# CM5_Adapter.net
KiCad netlist of a schematic drawn in Altium Designer
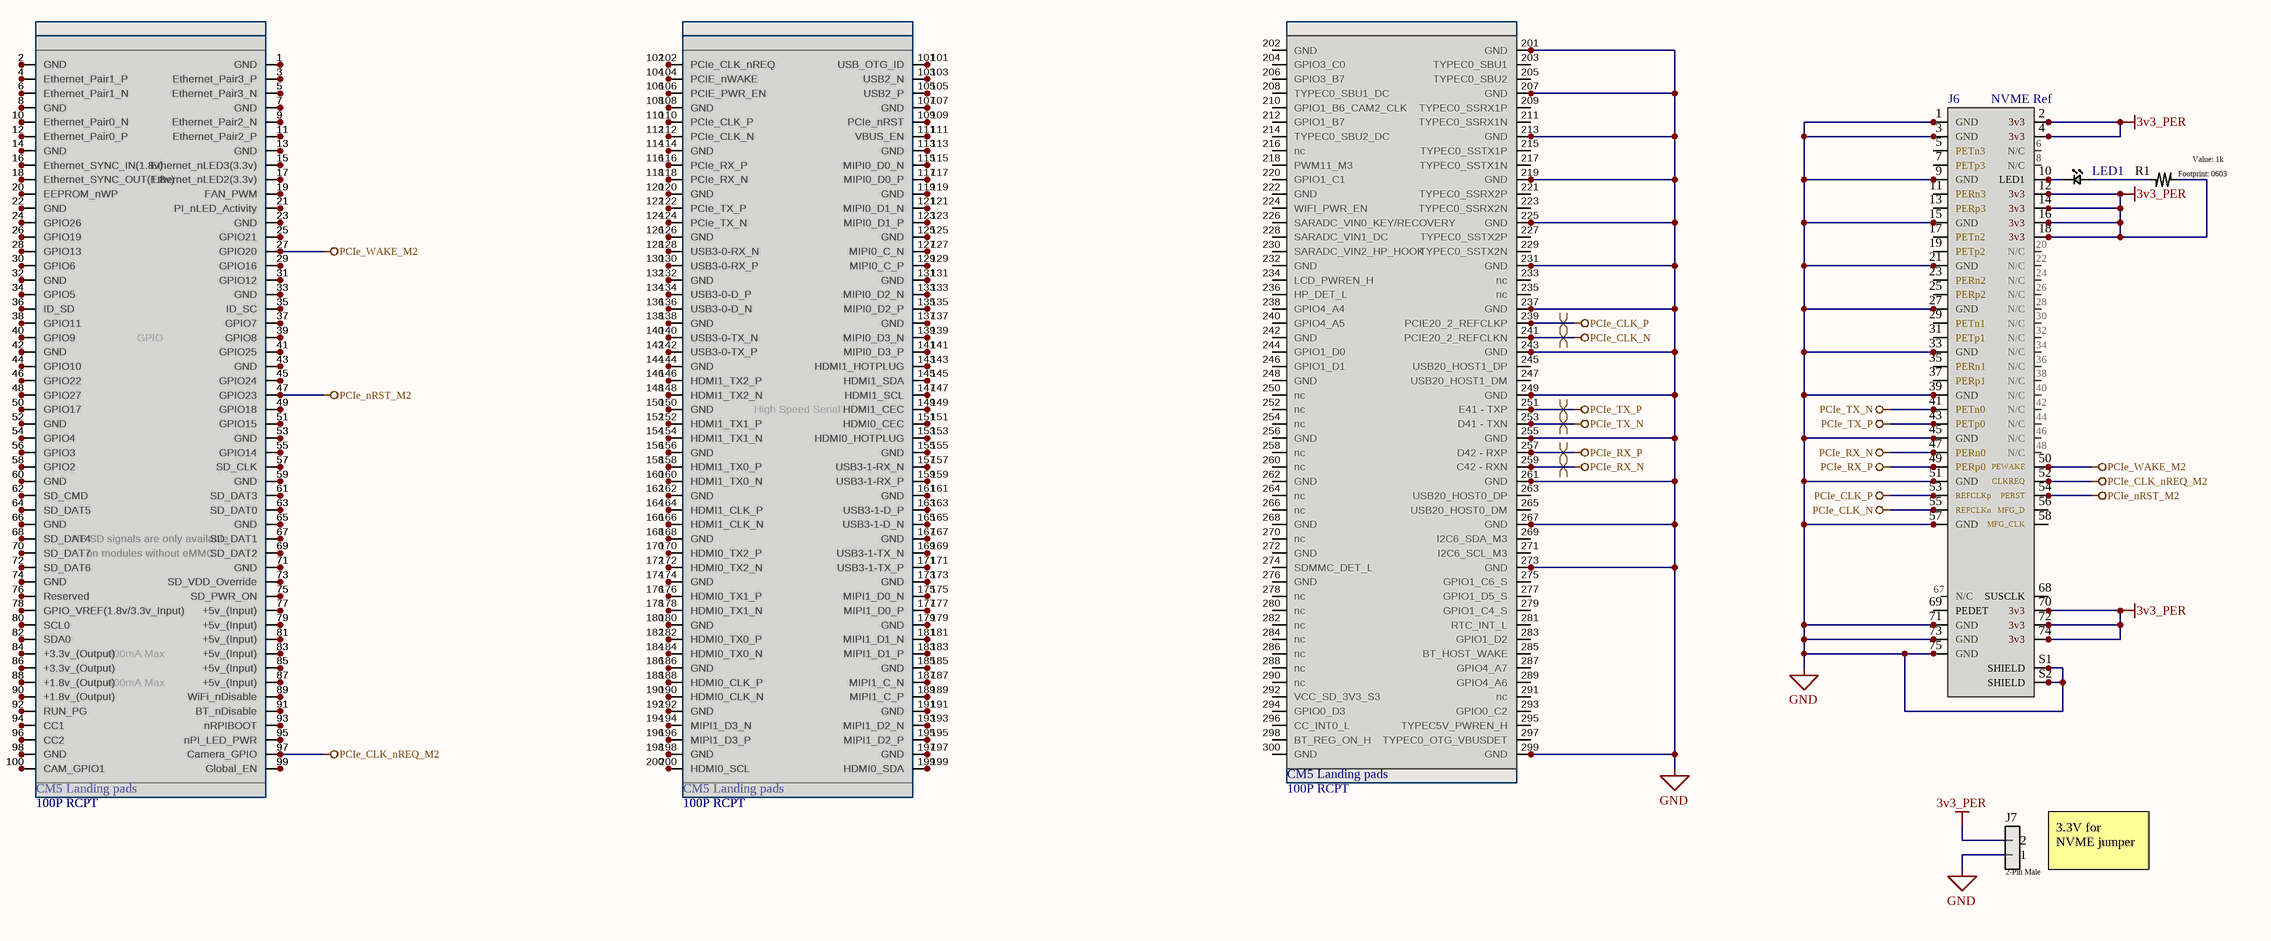
[diagram p0: CM5 Adapter.SchDoc]

(export (version "E")
  (design (tool "Eeschema 10.0.6"))
  (components
    (comp (ref "J1")
      (value "100P RCPT")
      (footprint "DF40C-100DP-0.4V(51)")
      (description "100 Position Connector Receptacle, Center Strip Contacts Surface Mount Gold")
      (fields (field (name "MF") "Hirose") (field (name "MP") "DF40C-100DS-0.4V(51)"))
      (libsource (lib "SOC_Carrier") (part "DF40-XX-100DS RCPT"))
    )
    (comp (ref "J2")
      (value "100P RCPT")
      (footprint "DF40C-100DP-0.4V(51)")
      (description "100 Position Connector Receptacle, Center Strip Contacts Surface Mount Gold")
      (fields (field (name "MF") "Hirose") (field (name "MP") "DF40C-100DS-0.4V(51)"))
      (libsource (lib "SOC_Carrier") (part "DF40-XX-100DS RCPT"))
    )
    (comp (ref "J3")
      (value "100P RCPT")
      (footprint "DF40HC(3.0)-100DS-0.4V(51)")
      (description "100 Position Connector Receptacle, Center Strip Contacts Surface Mount Gold")
      (fields (field (name "MF") "Hirose") (field (name "MP") "DF40C-100DS-0.4V(51)"))
      (libsource (lib "") (part "DF40-100DS RCPT_1_1"))
    )
    (comp (ref "J4")
      (value "100P RCPT")
      (footprint "DF40HC(3.0)-100DS-0.4V(51)")
      (description "100 Position Connector Receptacle, Center Strip Contacts Surface Mount Gold")
      (fields (field (name "MF") "Hirose") (field (name "MP") "DF40C-100DS-0.4V(51)"))
      (libsource (lib "Connectors") (part "DF40-100DS RCPT_1"))
    )
    (comp (ref "J5")
      (value "100P RCPT")
      (footprint "DF40HC(3.0)-100DS-0.4V(51)")
      (description "100 Position Connector Receptacle, Center Strip Contacts Surface Mount Gold")
      (fields (field (name "MF") "Hirose") (field (name "MP") "DF40C-100DS-0.4V(51)"))
      (libsource (lib "Connectors") (part "DF40-100DS RCPT_1"))
    )
    (comp (ref "J6")
      (value "M.2 M KEY")
      (footprint "1-2199230-6")
      (description "M.2 0.5PITCH 4.2H KEY M 30U AU")
      (fields (field (name "MF") "TE Connectivity") (field (name "DIGI-KEY_PART_NUMBER") "A118046TR-ND"))
      (libsource (lib "SOC_Carrier") (part "1-2199230-6_1"))
    )
    (comp (ref "J7")
      (value "2-Pin Male")
      (footprint "0022057025")
      (description "Conn Shrouded Header (4 Sides) HDR 2 POS 2.5mm Solder RA Thru-Hole SPOX™ Bag")
      (libsource (lib "Connectors") (part "0022057025"))
    )
    (comp (ref "LED1")
      (value "LTST-C191KGKT")
      (footprint "0603 (1608 Metric) Concave")
      (description "LED Uni-Color Green 574nm 2-Pin Chip LED T/R")
      (libsource (lib "Gamber - Johnson LLC") (part "LTST-C191KGKT"))
    )
    (comp (ref "M.1")
      (value "NVME Ref")
      (footprint "NVME-Ref")
      (description "Overlay pads w/ 1-2199230-6\r\nUse standoff for mounting screws")
      (libsource (lib "SOC_Carrier") (part "NVME Ref"))
    )
    (comp (ref "R1")
      (value "1k")
      (footprint "0603")
      (fields
        (field (name "TOLERANCE") "1%")
        (field (name "POWER") "1/10W")
        (field (name "Comment") "Generic Resistor")
      )
      (libsource (lib "Resistors") (part "Generic Resistor"))
    )
    (comp (ref "rPI1")
      (value "CM5 Landing pads")
      (footprint "rP-200P-CM-REP")
      (libsource (lib "SOC_Carrier") (part "RP-CM5-Rep"))
    )
    (comp (ref "rxPI1")
      (value "CM5 Landing pads")
      (footprint "RX-300P-CM-FTPD")
      (libsource (lib "SOC_Carrier") (part "RX-CM5"))
    )
  )
  (nets
    (net (code "1") (name "3v3_PER") (class "Default")
      (node (ref "J6") (pin "12") (pinfunction "3v3_12") (pintype "passive"))
      (node (ref "J6") (pin "14") (pinfunction "3v3_14") (pintype "passive"))
      (node (ref "J6") (pin "16") (pinfunction "3v3_16") (pintype "passive"))
      (node (ref "J6") (pin "18") (pinfunction "3v3_18") (pintype "passive"))
      (node (ref "J6") (pin "2") (pinfunction "3v3_2") (pintype "passive"))
      (node (ref "J6") (pin "4") (pinfunction "3v3_4") (pintype "passive"))
      (node (ref "J6") (pin "70") (pinfunction "3v3_70") (pintype "passive"))
      (node (ref "J6") (pin "72") (pinfunction "3v3_72") (pintype "passive"))
      (node (ref "J6") (pin "74") (pinfunction "3v3_74") (pintype "passive"))
      (node (ref "J7") (pin "2") (pinfunction "2_2") (pintype "passive"))
      (node (ref "M.1") (pin "12") (pinfunction "3v3_12") (pintype "passive"))
      (node (ref "M.1") (pin "14") (pinfunction "3v3_14") (pintype "passive"))
      (node (ref "M.1") (pin "16") (pinfunction "3v3_16") (pintype "passive"))
      (node (ref "M.1") (pin "18") (pinfunction "3v3_18") (pintype "passive"))
      (node (ref "M.1") (pin "2") (pinfunction "3v3_2") (pintype "passive"))
      (node (ref "M.1") (pin "4") (pinfunction "3v3_4") (pintype "passive"))
      (node (ref "M.1") (pin "70") (pinfunction "3v3_70") (pintype "passive"))
      (node (ref "M.1") (pin "72") (pinfunction "3v3_72") (pintype "passive"))
      (node (ref "M.1") (pin "74") (pinfunction "3v3_74") (pintype "passive"))
      (node (ref "R1") (pin "2") (pinfunction "2_2") (pintype "passive"))
    )
    (net (code "2") (name "GND") (class "Default")
      (node (ref "J3") (pin "100") (pinfunction "100_100") (pintype "passive"))
      (node (ref "J3") (pin "14") (pinfunction "14_14") (pintype "passive"))
      (node (ref "J3") (pin "2") (pinfunction "2_2") (pintype "passive"))
      (node (ref "J3") (pin "20") (pinfunction "20_20") (pintype "passive"))
      (node (ref "J3") (pin "26") (pinfunction "26_26") (pintype "passive"))
      (node (ref "J3") (pin "32") (pinfunction "32_32") (pintype "passive"))
      (node (ref "J3") (pin "38") (pinfunction "38_38") (pintype "passive"))
      (node (ref "J3") (pin "44") (pinfunction "44_44") (pintype "passive"))
      (node (ref "J3") (pin "50") (pinfunction "50_50") (pintype "passive"))
      (node (ref "J3") (pin "56") (pinfunction "56_56") (pintype "passive"))
      (node (ref "J3") (pin "62") (pinfunction "62_62") (pintype "passive"))
      (node (ref "J3") (pin "68") (pinfunction "68_68") (pintype "passive"))
      (node (ref "J3") (pin "74") (pinfunction "74_74") (pintype "passive"))
      (node (ref "J3") (pin "8") (pinfunction "8_8") (pintype "passive"))
      (node (ref "J6") (pin "1") (pinfunction "GND_1") (pintype "passive"))
      (node (ref "J6") (pin "15") (pinfunction "GND_15") (pintype "passive"))
      (node (ref "J6") (pin "21") (pinfunction "GND_21") (pintype "passive"))
      (node (ref "J6") (pin "27") (pinfunction "GND_27") (pintype "passive"))
      (node (ref "J6") (pin "3") (pinfunction "GND_3") (pintype "passive"))
      (node (ref "J6") (pin "33") (pinfunction "GND_33") (pintype "passive"))
      (node (ref "J6") (pin "39") (pinfunction "GND_39") (pintype "passive"))
      (node (ref "J6") (pin "45") (pinfunction "GND_45") (pintype "passive"))
      (node (ref "J6") (pin "51") (pinfunction "GND_51") (pintype "passive"))
      (node (ref "J6") (pin "57") (pinfunction "GND_57") (pintype "passive"))
      (node (ref "J6") (pin "71") (pinfunction "GND_71") (pintype "passive"))
      (node (ref "J6") (pin "73") (pinfunction "GND_73") (pintype "passive"))
      (node (ref "J6") (pin "75") (pinfunction "GND_75") (pintype "passive"))
      (node (ref "J6") (pin "9") (pinfunction "GND_9") (pintype "passive"))
      (node (ref "J6") (pin "S1") (pinfunction "SHIELD_S1") (pintype "passive"))
      (node (ref "J6") (pin "S2") (pinfunction "SHIELD_S2") (pintype "passive"))
      (node (ref "J7") (pin "1") (pinfunction "1_1") (pintype "passive"))
      (node (ref "M.1") (pin "1") (pinfunction "GND_1") (pintype "passive"))
      (node (ref "M.1") (pin "15") (pinfunction "GND_15") (pintype "passive"))
      (node (ref "M.1") (pin "21") (pinfunction "GND_21") (pintype "passive"))
      (node (ref "M.1") (pin "27") (pinfunction "GND_27") (pintype "passive"))
      (node (ref "M.1") (pin "3") (pinfunction "GND_3") (pintype "passive"))
      (node (ref "M.1") (pin "33") (pinfunction "GND_33") (pintype "passive"))
      (node (ref "M.1") (pin "39") (pinfunction "GND_39") (pintype "passive"))
      (node (ref "M.1") (pin "45") (pinfunction "GND_45") (pintype "passive"))
      (node (ref "M.1") (pin "51") (pinfunction "GND_51") (pintype "passive"))
      (node (ref "M.1") (pin "57") (pinfunction "GND_57") (pintype "passive"))
      (node (ref "M.1") (pin "71") (pinfunction "GND_71") (pintype "passive"))
      (node (ref "M.1") (pin "73") (pinfunction "GND_73") (pintype "passive"))
      (node (ref "M.1") (pin "75") (pinfunction "GND_75") (pintype "passive"))
      (node (ref "M.1") (pin "9") (pinfunction "GND_9") (pintype "passive"))
      (node (ref "M.1") (pin "S1") (pinfunction "SHIELD_S1") (pintype "passive"))
      (node (ref "M.1") (pin "S2") (pinfunction "SHIELD_S2") (pintype "passive"))
      (node (ref "M.1") (pin "SHD") (pinfunction "SHIELD_SHD") (pintype "passive"))
      (node (ref "rxPI1") (pin "201") (pinfunction "GND_201") (pintype "passive"))
      (node (ref "rxPI1") (pin "207") (pinfunction "GND_207") (pintype "passive"))
      (node (ref "rxPI1") (pin "213") (pinfunction "GND_213") (pintype "passive"))
      (node (ref "rxPI1") (pin "219") (pinfunction "GND_219") (pintype "passive"))
      (node (ref "rxPI1") (pin "225") (pinfunction "GND_225") (pintype "passive"))
      (node (ref "rxPI1") (pin "231") (pinfunction "GND_231") (pintype "passive"))
      (node (ref "rxPI1") (pin "237") (pinfunction "GND_237") (pintype "passive"))
      (node (ref "rxPI1") (pin "243") (pinfunction "GND_243") (pintype "passive"))
      (node (ref "rxPI1") (pin "249") (pinfunction "GND_249") (pintype "passive"))
      (node (ref "rxPI1") (pin "255") (pinfunction "GND_255") (pintype "passive"))
      (node (ref "rxPI1") (pin "261") (pinfunction "GND_261") (pintype "passive"))
      (node (ref "rxPI1") (pin "267") (pinfunction "GND_267") (pintype "passive"))
      (node (ref "rxPI1") (pin "273") (pinfunction "GND_273") (pintype "passive"))
      (node (ref "rxPI1") (pin "299") (pinfunction "GND_299") (pintype "passive"))
    )
    (net (code "3") (name "Net-(J1-Pad1)") (class "Default")
      (node (ref "J1") (pin "1") (pinfunction "1_1") (pintype "passive"))
      (node (ref "J4") (pin "2") (pinfunction "2_2") (pintype "passive"))
      (node (ref "rPI1") (pin "2") (pinfunction "GND_2") (pintype "passive"))
      (node (ref "rxPI1") (pin "2") (pinfunction "GND_2") (pintype "passive"))
    )
    (net (code "4") (name "Net-(J1-Pad2)") (class "Default")
      (node (ref "J1") (pin "2") (pinfunction "2_2") (pintype "passive"))
      (node (ref "J4") (pin "1") (pinfunction "1_1") (pintype "passive"))
      (node (ref "rPI1") (pin "1") (pinfunction "GND_1") (pintype "passive"))
      (node (ref "rxPI1") (pin "1") (pinfunction "GND_1") (pintype "passive"))
    )
    (net (code "5") (name "Net-(J1-Pad7)") (class "Default")
      (node (ref "J1") (pin "7") (pinfunction "7_7") (pintype "passive"))
      (node (ref "J4") (pin "8") (pinfunction "8_8") (pintype "passive"))
      (node (ref "rPI1") (pin "8") (pinfunction "GND_8") (pintype "passive"))
      (node (ref "rxPI1") (pin "8") (pinfunction "GND_8") (pintype "passive"))
    )
    (net (code "6") (name "Net-(J1-Pad8)") (class "Default")
      (node (ref "J1") (pin "8") (pinfunction "8_8") (pintype "passive"))
      (node (ref "J4") (pin "7") (pinfunction "7_7") (pintype "passive"))
      (node (ref "rPI1") (pin "7") (pinfunction "GND_7") (pintype "passive"))
      (node (ref "rxPI1") (pin "7") (pinfunction "GND_7") (pintype "passive"))
    )
    (net (code "7") (name "Net-(J1-Pad13)") (class "Default")
      (node (ref "J1") (pin "13") (pinfunction "13_13") (pintype "passive"))
      (node (ref "J4") (pin "14") (pinfunction "14_14") (pintype "passive"))
      (node (ref "rPI1") (pin "14") (pinfunction "GND_14") (pintype "passive"))
      (node (ref "rxPI1") (pin "14") (pinfunction "GND_14") (pintype "passive"))
    )
    (net (code "8") (name "Net-(J1-Pad14)") (class "Default")
      (node (ref "J1") (pin "14") (pinfunction "14_14") (pintype "passive"))
      (node (ref "J4") (pin "13") (pinfunction "13_13") (pintype "passive"))
      (node (ref "rPI1") (pin "13") (pinfunction "GND_13") (pintype "passive"))
      (node (ref "rxPI1") (pin "13") (pinfunction "GND_13") (pintype "passive"))
    )
    (net (code "9") (name "Net-(J1-Pad21)") (class "Default")
      (node (ref "J1") (pin "21") (pinfunction "21_21") (pintype "passive"))
      (node (ref "J4") (pin "22") (pinfunction "22_22") (pintype "passive"))
      (node (ref "rPI1") (pin "22") (pinfunction "GND_22") (pintype "passive"))
      (node (ref "rxPI1") (pin "22") (pinfunction "GND_22") (pintype "passive"))
    )
    (net (code "10") (name "Net-(J1-Pad24)") (class "Default")
      (node (ref "J1") (pin "24") (pinfunction "24_24") (pintype "passive"))
      (node (ref "J4") (pin "23") (pinfunction "23_23") (pintype "passive"))
      (node (ref "rPI1") (pin "23") (pinfunction "GND_23") (pintype "passive"))
      (node (ref "rxPI1") (pin "23") (pinfunction "GND_23") (pintype "passive"))
    )
    (net (code "11") (name "Net-(J1-Pad31)") (class "Default")
      (node (ref "J1") (pin "31") (pinfunction "31_31") (pintype "passive"))
      (node (ref "J4") (pin "32") (pinfunction "32_32") (pintype "passive"))
      (node (ref "rPI1") (pin "32") (pinfunction "GND_32") (pintype "passive"))
      (node (ref "rxPI1") (pin "32") (pinfunction "GND_32") (pintype "passive"))
    )
    (net (code "12") (name "Net-(J1-Pad34)") (class "Default")
      (node (ref "J1") (pin "34") (pinfunction "34_34") (pintype "passive"))
      (node (ref "J4") (pin "33") (pinfunction "33_33") (pintype "passive"))
      (node (ref "rPI1") (pin "33") (pinfunction "GND_33") (pintype "passive"))
      (node (ref "rxPI1") (pin "33") (pinfunction "GND_33") (pintype "passive"))
    )
    (net (code "13") (name "Net-(J1-Pad41)") (class "Default")
      (node (ref "J1") (pin "41") (pinfunction "41_41") (pintype "passive"))
      (node (ref "J4") (pin "42") (pinfunction "42_42") (pintype "passive"))
      (node (ref "rPI1") (pin "42") (pinfunction "GND_42") (pintype "passive"))
      (node (ref "rxPI1") (pin "42") (pinfunction "GND_42") (pintype "passive"))
    )
    (net (code "14") (name "Net-(J1-Pad44)") (class "Default")
      (node (ref "J1") (pin "44") (pinfunction "44_44") (pintype "passive"))
      (node (ref "J4") (pin "43") (pinfunction "43_43") (pintype "passive"))
      (node (ref "rPI1") (pin "43") (pinfunction "GND_43") (pintype "passive"))
      (node (ref "rxPI1") (pin "43") (pinfunction "GND_43") (pintype "passive"))
    )
    (net (code "15") (name "Net-(J1-Pad51)") (class "Default")
      (node (ref "J1") (pin "51") (pinfunction "51_51") (pintype "passive"))
      (node (ref "J4") (pin "52") (pinfunction "52_52") (pintype "passive"))
      (node (ref "rPI1") (pin "52") (pinfunction "GND_52") (pintype "passive"))
      (node (ref "rxPI1") (pin "52") (pinfunction "GND_52") (pintype "passive"))
    )
    (net (code "16") (name "Net-(J1-Pad54)") (class "Default")
      (node (ref "J1") (pin "54") (pinfunction "54_54") (pintype "passive"))
      (node (ref "J4") (pin "53") (pinfunction "53_53") (pintype "passive"))
      (node (ref "rPI1") (pin "53") (pinfunction "GND_53") (pintype "passive"))
      (node (ref "rxPI1") (pin "53") (pinfunction "GND_53") (pintype "passive"))
    )
    (net (code "17") (name "Net-(J1-Pad59)") (class "Default")
      (node (ref "J1") (pin "59") (pinfunction "59_59") (pintype "passive"))
      (node (ref "J4") (pin "60") (pinfunction "60_60") (pintype "passive"))
      (node (ref "rPI1") (pin "60") (pinfunction "GND_60") (pintype "passive"))
      (node (ref "rxPI1") (pin "60") (pinfunction "GND_60") (pintype "passive"))
    )
    (net (code "18") (name "Net-(J1-Pad60)") (class "Default")
      (node (ref "J1") (pin "60") (pinfunction "60_60") (pintype "passive"))
      (node (ref "J4") (pin "59") (pinfunction "59_59") (pintype "passive"))
      (node (ref "rPI1") (pin "59") (pinfunction "GND_59") (pintype "passive"))
      (node (ref "rxPI1") (pin "59") (pinfunction "GND_59") (pintype "passive"))
    )
    (net (code "19") (name "Net-(J1-Pad65)") (class "Default")
      (node (ref "J1") (pin "65") (pinfunction "65_65") (pintype "passive"))
      (node (ref "J4") (pin "66") (pinfunction "66_66") (pintype "passive"))
      (node (ref "rPI1") (pin "66") (pinfunction "GND_66") (pintype "passive"))
      (node (ref "rxPI1") (pin "66") (pinfunction "GND_66") (pintype "passive"))
    )
    (net (code "20") (name "Net-(J1-Pad66)") (class "Default")
      (node (ref "J1") (pin "66") (pinfunction "66_66") (pintype "passive"))
      (node (ref "J4") (pin "65") (pinfunction "65_65") (pintype "passive"))
      (node (ref "rPI1") (pin "65") (pinfunction "GND_65") (pintype "passive"))
      (node (ref "rxPI1") (pin "65") (pinfunction "GND_65") (pintype "passive"))
    )
    (net (code "21") (name "Net-(J1-Pad72)") (class "Default")
      (node (ref "J1") (pin "72") (pinfunction "72_72") (pintype "passive"))
      (node (ref "J4") (pin "71") (pinfunction "71_71") (pintype "passive"))
      (node (ref "rPI1") (pin "71") (pinfunction "GND_71") (pintype "passive"))
      (node (ref "rxPI1") (pin "71") (pinfunction "GND_71") (pintype "passive"))
    )
    (net (code "22") (name "Net-(J1-Pad73)") (class "Default")
      (node (ref "J1") (pin "73") (pinfunction "73_73") (pintype "passive"))
      (node (ref "J4") (pin "74") (pinfunction "74_74") (pintype "passive"))
      (node (ref "rPI1") (pin "74") (pinfunction "GND_74") (pintype "passive"))
      (node (ref "rxPI1") (pin "74") (pinfunction "GND_74") (pintype "passive"))
    )
    (net (code "23") (name "Net-(J1-Pad78)") (class "Default")
      (node (ref "J1") (pin "78") (pinfunction "78_78") (pintype "passive"))
      (node (ref "J4") (pin "77") (pinfunction "77_77") (pintype "passive"))
      (node (ref "rPI1") (pin "77") (pinfunction "+5v_(Input)_77") (pintype "passive"))
      (node (ref "rxPI1") (pin "77") (pinfunction "+5v_(Input)_77") (pintype "passive"))
    )
    (net (code "24") (name "Net-(J1-Pad80)") (class "Default")
      (node (ref "J1") (pin "80") (pinfunction "80_80") (pintype "passive"))
      (node (ref "J4") (pin "79") (pinfunction "79_79") (pintype "passive"))
      (node (ref "rPI1") (pin "79") (pinfunction "+5v_(Input)_79") (pintype "passive"))
      (node (ref "rxPI1") (pin "79") (pinfunction "+5v_(Input)_79") (pintype "passive"))
    )
    (net (code "25") (name "Net-(J1-Pad82)") (class "Default")
      (node (ref "J1") (pin "82") (pinfunction "82_82") (pintype "passive"))
      (node (ref "J4") (pin "81") (pinfunction "81_81") (pintype "passive"))
      (node (ref "rPI1") (pin "81") (pinfunction "+5v_(Input)_81") (pintype "passive"))
      (node (ref "rxPI1") (pin "81") (pinfunction "+5v_(Input)_81") (pintype "passive"))
    )
    (net (code "26") (name "Net-(J1-Pad83)") (class "Default")
      (node (ref "J1") (pin "83") (pinfunction "83_83") (pintype "passive"))
      (node (ref "J4") (pin "84") (pinfunction "84_84") (pintype "passive"))
      (node (ref "rPI1") (pin "84") (pinfunction "+3.3v_(Output)_84") (pintype "passive"))
      (node (ref "rxPI1") (pin "84") (pinfunction "+3.3v_(Output)_84") (pintype "passive"))
    )
    (net (code "27") (name "Net-(J1-Pad84)") (class "Default")
      (node (ref "J1") (pin "84") (pinfunction "84_84") (pintype "passive"))
      (node (ref "J4") (pin "83") (pinfunction "83_83") (pintype "passive"))
      (node (ref "rPI1") (pin "83") (pinfunction "+5v_(Input)_83") (pintype "passive"))
      (node (ref "rxPI1") (pin "83") (pinfunction "+5v_(Input)_83") (pintype "passive"))
    )
    (net (code "28") (name "Net-(J1-Pad85)") (class "Default")
      (node (ref "J1") (pin "85") (pinfunction "85_85") (pintype "passive"))
      (node (ref "J4") (pin "86") (pinfunction "86_86") (pintype "passive"))
      (node (ref "rPI1") (pin "86") (pinfunction "+3.3v_(Output)_86") (pintype "passive"))
      (node (ref "rxPI1") (pin "86") (pinfunction "+3.3v_(Output)_86") (pintype "passive"))
    )
    (net (code "29") (name "Net-(J1-Pad86)") (class "Default")
      (node (ref "J1") (pin "86") (pinfunction "86_86") (pintype "passive"))
      (node (ref "J4") (pin "85") (pinfunction "85_85") (pintype "passive"))
      (node (ref "rPI1") (pin "85") (pinfunction "+5v_(Input)_85") (pintype "passive"))
      (node (ref "rxPI1") (pin "85") (pinfunction "+5v_(Input)_85") (pintype "passive"))
    )
    (net (code "30") (name "Net-(J1-Pad87)") (class "Default")
      (node (ref "J1") (pin "87") (pinfunction "87_87") (pintype "passive"))
      (node (ref "J4") (pin "88") (pinfunction "88_88") (pintype "passive"))
      (node (ref "rPI1") (pin "88") (pinfunction "+1.8v_(Output)_88") (pintype "passive"))
      (node (ref "rxPI1") (pin "88") (pinfunction "+1.8v_(Output)_88") (pintype "passive"))
    )
    (net (code "31") (name "Net-(J1-Pad88)") (class "Default")
      (node (ref "J1") (pin "88") (pinfunction "88_88") (pintype "passive"))
      (node (ref "J4") (pin "87") (pinfunction "87_87") (pintype "passive"))
      (node (ref "rPI1") (pin "87") (pinfunction "+5v_(Input)_87") (pintype "passive"))
      (node (ref "rxPI1") (pin "87") (pinfunction "+5v_(Input)_87") (pintype "passive"))
    )
    (net (code "32") (name "Net-(J1-Pad89)") (class "Default")
      (node (ref "J1") (pin "89") (pinfunction "89_89") (pintype "passive"))
      (node (ref "J4") (pin "90") (pinfunction "90_90") (pintype "passive"))
      (node (ref "rPI1") (pin "90") (pinfunction "+1.8v_(Output)_90") (pintype "passive"))
      (node (ref "rxPI1") (pin "90") (pinfunction "+1.8v_(Output)_90") (pintype "passive"))
    )
    (net (code "33") (name "Net-(J1-Pad97)") (class "Default")
      (node (ref "J1") (pin "97") (pinfunction "97_97") (pintype "passive"))
      (node (ref "J4") (pin "98") (pinfunction "98_98") (pintype "passive"))
      (node (ref "rPI1") (pin "98") (pinfunction "GND_98") (pintype "passive"))
      (node (ref "rxPI1") (pin "98") (pinfunction "GND_98") (pintype "passive"))
    )
    (net (code "34") (name "Net-(J2-Pad7)") (class "Default")
      (node (ref "J2") (pin "7") (pinfunction "7_7") (pintype "passive"))
      (node (ref "J5") (pin "8") (pinfunction "8_8") (pintype "passive"))
      (node (ref "rPI1") (pin "108") (pinfunction "GND_108") (pintype "passive"))
      (node (ref "rxPI1") (pin "108") (pinfunction "GND_108") (pintype "passive"))
    )
    (net (code "35") (name "Net-(J2-Pad8)") (class "Default")
      (node (ref "J2") (pin "8") (pinfunction "8_8") (pintype "passive"))
      (node (ref "J5") (pin "7") (pinfunction "7_7") (pintype "passive"))
      (node (ref "rPI1") (pin "107") (pinfunction "GND_107") (pintype "passive"))
      (node (ref "rxPI1") (pin "107") (pinfunction "GND_107") (pintype "passive"))
    )
    (net (code "36") (name "Net-(J2-Pad13)") (class "Default")
      (node (ref "J2") (pin "13") (pinfunction "13_13") (pintype "passive"))
      (node (ref "J5") (pin "14") (pinfunction "14_14") (pintype "passive"))
      (node (ref "rPI1") (pin "114") (pinfunction "GND_114") (pintype "passive"))
      (node (ref "rxPI1") (pin "114") (pinfunction "GND_114") (pintype "passive"))
    )
    (net (code "37") (name "Net-(J2-Pad14)") (class "Default")
      (node (ref "J2") (pin "14") (pinfunction "14_14") (pintype "passive"))
      (node (ref "J5") (pin "13") (pinfunction "13_13") (pintype "passive"))
      (node (ref "rPI1") (pin "113") (pinfunction "GND_113") (pintype "passive"))
      (node (ref "rxPI1") (pin "113") (pinfunction "GND_113") (pintype "passive"))
    )
    (net (code "38") (name "Net-(J2-Pad19)") (class "Default")
      (node (ref "J2") (pin "19") (pinfunction "19_19") (pintype "passive"))
      (node (ref "J5") (pin "20") (pinfunction "20_20") (pintype "passive"))
      (node (ref "rPI1") (pin "120") (pinfunction "GND_120") (pintype "passive"))
      (node (ref "rxPI1") (pin "120") (pinfunction "GND_120") (pintype "passive"))
    )
    (net (code "39") (name "Net-(J2-Pad20)") (class "Default")
      (node (ref "J2") (pin "20") (pinfunction "20_20") (pintype "passive"))
      (node (ref "J5") (pin "19") (pinfunction "19_19") (pintype "passive"))
      (node (ref "rPI1") (pin "119") (pinfunction "GND_119") (pintype "passive"))
      (node (ref "rxPI1") (pin "119") (pinfunction "GND_119") (pintype "passive"))
    )
    (net (code "40") (name "Net-(J2-Pad25)") (class "Default")
      (node (ref "J2") (pin "25") (pinfunction "25_25") (pintype "passive"))
      (node (ref "J5") (pin "26") (pinfunction "26_26") (pintype "passive"))
      (node (ref "rPI1") (pin "126") (pinfunction "GND_126") (pintype "passive"))
      (node (ref "rxPI1") (pin "126") (pinfunction "GND_126") (pintype "passive"))
    )
    (net (code "41") (name "Net-(J2-Pad26)") (class "Default")
      (node (ref "J2") (pin "26") (pinfunction "26_26") (pintype "passive"))
      (node (ref "J5") (pin "25") (pinfunction "25_25") (pintype "passive"))
      (node (ref "rPI1") (pin "125") (pinfunction "GND_125") (pintype "passive"))
      (node (ref "rxPI1") (pin "125") (pinfunction "GND_125") (pintype "passive"))
    )
    (net (code "42") (name "Net-(J2-Pad31)") (class "Default")
      (node (ref "J2") (pin "31") (pinfunction "31_31") (pintype "passive"))
      (node (ref "J5") (pin "32") (pinfunction "32_32") (pintype "passive"))
      (node (ref "rPI1") (pin "132") (pinfunction "GND_132") (pintype "passive"))
      (node (ref "rxPI1") (pin "132") (pinfunction "GND_132") (pintype "passive"))
    )
    (net (code "43") (name "Net-(J2-Pad32)") (class "Default")
      (node (ref "J2") (pin "32") (pinfunction "32_32") (pintype "passive"))
      (node (ref "J5") (pin "31") (pinfunction "31_31") (pintype "passive"))
      (node (ref "rPI1") (pin "131") (pinfunction "GND_131") (pintype "passive"))
      (node (ref "rxPI1") (pin "131") (pinfunction "GND_131") (pintype "passive"))
    )
    (net (code "44") (name "Net-(J2-Pad37)") (class "Default")
      (node (ref "J2") (pin "37") (pinfunction "37_37") (pintype "passive"))
      (node (ref "J5") (pin "38") (pinfunction "38_38") (pintype "passive"))
      (node (ref "rPI1") (pin "138") (pinfunction "GND_138") (pintype "passive"))
      (node (ref "rxPI1") (pin "138") (pinfunction "GND_138") (pintype "passive"))
    )
    (net (code "45") (name "Net-(J2-Pad38)") (class "Default")
      (node (ref "J2") (pin "38") (pinfunction "38_38") (pintype "passive"))
      (node (ref "J5") (pin "37") (pinfunction "37_37") (pintype "passive"))
      (node (ref "rPI1") (pin "137") (pinfunction "GND_137") (pintype "passive"))
      (node (ref "rxPI1") (pin "137") (pinfunction "GND_137") (pintype "passive"))
    )
    (net (code "46") (name "Net-(J2-Pad43)") (class "Default")
      (node (ref "J2") (pin "43") (pinfunction "43_43") (pintype "passive"))
      (node (ref "J5") (pin "44") (pinfunction "44_44") (pintype "passive"))
      (node (ref "rPI1") (pin "144") (pinfunction "GND_144") (pintype "passive"))
      (node (ref "rxPI1") (pin "144") (pinfunction "GND_144") (pintype "passive"))
    )
    (net (code "47") (name "Net-(J2-Pad49)") (class "Default")
      (node (ref "J2") (pin "49") (pinfunction "49_49") (pintype "passive"))
      (node (ref "J5") (pin "50") (pinfunction "50_50") (pintype "passive"))
      (node (ref "rPI1") (pin "150") (pinfunction "GND_150") (pintype "passive"))
      (node (ref "rxPI1") (pin "150") (pinfunction "GND_150") (pintype "passive"))
    )
    (net (code "48") (name "Net-(J2-Pad55)") (class "Default")
      (node (ref "J2") (pin "55") (pinfunction "55_55") (pintype "passive"))
      (node (ref "J5") (pin "56") (pinfunction "56_56") (pintype "passive"))
      (node (ref "rPI1") (pin "156") (pinfunction "GND_156") (pintype "passive"))
      (node (ref "rxPI1") (pin "156") (pinfunction "GND_156") (pintype "passive"))
    )
    (net (code "49") (name "Net-(J2-Pad56)") (class "Default")
      (node (ref "J2") (pin "56") (pinfunction "56_56") (pintype "passive"))
      (node (ref "J5") (pin "55") (pinfunction "55_55") (pintype "passive"))
      (node (ref "rPI1") (pin "155") (pinfunction "GND_155") (pintype "passive"))
      (node (ref "rxPI1") (pin "155") (pinfunction "GND_155") (pintype "passive"))
    )
    (net (code "50") (name "Net-(J2-Pad61)") (class "Default")
      (node (ref "J2") (pin "61") (pinfunction "61_61") (pintype "passive"))
      (node (ref "J5") (pin "62") (pinfunction "62_62") (pintype "passive"))
      (node (ref "rPI1") (pin "162") (pinfunction "GND_162") (pintype "passive"))
      (node (ref "rxPI1") (pin "162") (pinfunction "GND_162") (pintype "passive"))
    )
    (net (code "51") (name "Net-(J2-Pad62)") (class "Default")
      (node (ref "J2") (pin "62") (pinfunction "62_62") (pintype "passive"))
      (node (ref "J5") (pin "61") (pinfunction "61_61") (pintype "passive"))
      (node (ref "rPI1") (pin "161") (pinfunction "GND_161") (pintype "passive"))
      (node (ref "rxPI1") (pin "161") (pinfunction "GND_161") (pintype "passive"))
    )
    (net (code "52") (name "Net-(J2-Pad67)") (class "Default")
      (node (ref "J2") (pin "67") (pinfunction "67_67") (pintype "passive"))
      (node (ref "J5") (pin "68") (pinfunction "68_68") (pintype "passive"))
      (node (ref "rPI1") (pin "168") (pinfunction "GND_168") (pintype "passive"))
      (node (ref "rxPI1") (pin "168") (pinfunction "GND_168") (pintype "passive"))
    )
    (net (code "53") (name "Net-(J2-Pad68)") (class "Default")
      (node (ref "J2") (pin "68") (pinfunction "68_68") (pintype "passive"))
      (node (ref "J5") (pin "67") (pinfunction "67_67") (pintype "passive"))
      (node (ref "rPI1") (pin "167") (pinfunction "GND_167") (pintype "passive"))
      (node (ref "rxPI1") (pin "167") (pinfunction "GND_167") (pintype "passive"))
    )
    (net (code "54") (name "Net-(J2-Pad73)") (class "Default")
      (node (ref "J2") (pin "73") (pinfunction "73_73") (pintype "passive"))
      (node (ref "J5") (pin "74") (pinfunction "74_74") (pintype "passive"))
      (node (ref "rPI1") (pin "174") (pinfunction "GND_174") (pintype "passive"))
      (node (ref "rxPI1") (pin "174") (pinfunction "GND_174") (pintype "passive"))
    )
    (net (code "55") (name "Net-(J2-Pad74)") (class "Default")
      (node (ref "J2") (pin "74") (pinfunction "74_74") (pintype "passive"))
      (node (ref "J5") (pin "73") (pinfunction "73_73") (pintype "passive"))
      (node (ref "rPI1") (pin "173") (pinfunction "GND_173") (pintype "passive"))
      (node (ref "rxPI1") (pin "173") (pinfunction "GND_173") (pintype "passive"))
    )
    (net (code "56") (name "Net-(J2-Pad79)") (class "Default")
      (node (ref "J2") (pin "79") (pinfunction "79_79") (pintype "passive"))
      (node (ref "J5") (pin "80") (pinfunction "80_80") (pintype "passive"))
      (node (ref "rPI1") (pin "180") (pinfunction "GND_180") (pintype "passive"))
      (node (ref "rxPI1") (pin "180") (pinfunction "GND_180") (pintype "passive"))
    )
    (net (code "57") (name "Net-(J2-Pad80)") (class "Default")
      (node (ref "J2") (pin "80") (pinfunction "80_80") (pintype "passive"))
      (node (ref "J5") (pin "79") (pinfunction "79_79") (pintype "passive"))
      (node (ref "rPI1") (pin "179") (pinfunction "GND_179") (pintype "passive"))
      (node (ref "rxPI1") (pin "179") (pinfunction "GND_179") (pintype "passive"))
    )
    (net (code "58") (name "Net-(J2-Pad85)") (class "Default")
      (node (ref "J2") (pin "85") (pinfunction "85_85") (pintype "passive"))
      (node (ref "J5") (pin "86") (pinfunction "86_86") (pintype "passive"))
      (node (ref "rPI1") (pin "186") (pinfunction "GND_186") (pintype "passive"))
      (node (ref "rxPI1") (pin "186") (pinfunction "GND_186") (pintype "passive"))
    )
    (net (code "59") (name "Net-(J2-Pad86)") (class "Default")
      (node (ref "J2") (pin "86") (pinfunction "86_86") (pintype "passive"))
      (node (ref "J5") (pin "85") (pinfunction "85_85") (pintype "passive"))
      (node (ref "rPI1") (pin "185") (pinfunction "GND_185") (pintype "passive"))
      (node (ref "rxPI1") (pin "185") (pinfunction "GND_185") (pintype "passive"))
    )
    (net (code "60") (name "Net-(J2-Pad91)") (class "Default")
      (node (ref "J2") (pin "91") (pinfunction "91_91") (pintype "passive"))
      (node (ref "J5") (pin "92") (pinfunction "92_92") (pintype "passive"))
      (node (ref "rPI1") (pin "192") (pinfunction "GND_192") (pintype "passive"))
      (node (ref "rxPI1") (pin "192") (pinfunction "GND_192") (pintype "passive"))
    )
    (net (code "61") (name "Net-(J2-Pad92)") (class "Default")
      (node (ref "J2") (pin "92") (pinfunction "92_92") (pintype "passive"))
      (node (ref "J5") (pin "91") (pinfunction "91_91") (pintype "passive"))
      (node (ref "rPI1") (pin "191") (pinfunction "GND_191") (pintype "passive"))
      (node (ref "rxPI1") (pin "191") (pinfunction "GND_191") (pintype "passive"))
    )
    (net (code "62") (name "Net-(J2-Pad97)") (class "Default")
      (node (ref "J2") (pin "97") (pinfunction "97_97") (pintype "passive"))
      (node (ref "J5") (pin "98") (pinfunction "98_98") (pintype "passive"))
      (node (ref "rPI1") (pin "198") (pinfunction "GND_198") (pintype "passive"))
      (node (ref "rxPI1") (pin "198") (pinfunction "GND_198") (pintype "passive"))
    )
    (net (code "63") (name "Net-(J2-Pad98)") (class "Default")
      (node (ref "J2") (pin "98") (pinfunction "98_98") (pintype "passive"))
      (node (ref "J5") (pin "97") (pinfunction "97_97") (pintype "passive"))
      (node (ref "rPI1") (pin "197") (pinfunction "GND_197") (pintype "passive"))
      (node (ref "rxPI1") (pin "197") (pinfunction "GND_197") (pintype "passive"))
    )
    (net (code "64") (name "Net-(J3-Pad1)") (class "Default")
      (node (ref "J3") (pin "1") (pinfunction "1_1") (pintype "passive"))
      (node (ref "rxPI1") (pin "202") (pinfunction "GND_202") (pintype "passive"))
    )
    (net (code "65") (name "Net-(J3-Pad15)") (class "Default")
      (node (ref "J3") (pin "15") (pinfunction "15_15") (pintype "passive"))
      (node (ref "rxPI1") (pin "216") (pinfunction "nc_216") (pintype "passive"))
    )
    (net (code "66") (name "Net-(J3-Pad21)") (class "Default")
      (node (ref "J3") (pin "21") (pinfunction "21_21") (pintype "passive"))
      (node (ref "rxPI1") (pin "222") (pinfunction "GND_222") (pintype "passive"))
    )
    (net (code "67") (name "Net-(J3-Pad31)") (class "Default")
      (node (ref "J3") (pin "31") (pinfunction "31_31") (pintype "passive"))
      (node (ref "rxPI1") (pin "232") (pinfunction "GND_232") (pintype "passive"))
    )
    (net (code "68") (name "Net-(J3-Pad34)") (class "Default")
      (node (ref "J3") (pin "34") (pinfunction "34_34") (pintype "passive"))
      (node (ref "rxPI1") (pin "233") (pinfunction "nc_233") (pintype "passive"))
    )
    (net (code "69") (name "Net-(J3-Pad36)") (class "Default")
      (node (ref "J3") (pin "36") (pinfunction "36_36") (pintype "passive"))
      (node (ref "rxPI1") (pin "235") (pinfunction "nc_235") (pintype "passive"))
    )
    (net (code "70") (name "Net-(J3-Pad41)") (class "Default")
      (node (ref "J3") (pin "41") (pinfunction "41_41") (pintype "passive"))
      (node (ref "rxPI1") (pin "242") (pinfunction "GND_242") (pintype "passive"))
    )
    (net (code "71") (name "Net-(J3-Pad47)") (class "Default")
      (node (ref "J3") (pin "47") (pinfunction "47_47") (pintype "passive"))
      (node (ref "rxPI1") (pin "248") (pinfunction "GND_248") (pintype "passive"))
    )
    (net (code "72") (name "Net-(J3-Pad49)") (class "Default")
      (node (ref "J3") (pin "49") (pinfunction "49_49") (pintype "passive"))
      (node (ref "rxPI1") (pin "250") (pinfunction "nc_250") (pintype "passive"))
    )
    (net (code "73") (name "Net-(J3-Pad51)") (class "Default")
      (node (ref "J3") (pin "51") (pinfunction "51_51") (pintype "passive"))
      (node (ref "rxPI1") (pin "252") (pinfunction "nc_252") (pintype "passive"))
    )
    (net (code "74") (name "Net-(J3-Pad53)") (class "Default")
      (node (ref "J3") (pin "53") (pinfunction "53_53") (pintype "passive"))
      (node (ref "rxPI1") (pin "254") (pinfunction "nc_254") (pintype "passive"))
    )
    (net (code "75") (name "Net-(J3-Pad55)") (class "Default")
      (node (ref "J3") (pin "55") (pinfunction "55_55") (pintype "passive"))
      (node (ref "rxPI1") (pin "256") (pinfunction "GND_256") (pintype "passive"))
    )
    (net (code "76") (name "Net-(J3-Pad57)") (class "Default")
      (node (ref "J3") (pin "57") (pinfunction "57_57") (pintype "passive"))
      (node (ref "rxPI1") (pin "258") (pinfunction "nc_258") (pintype "passive"))
    )
    (net (code "77") (name "Net-(J3-Pad59)") (class "Default")
      (node (ref "J3") (pin "59") (pinfunction "59_59") (pintype "passive"))
      (node (ref "rxPI1") (pin "260") (pinfunction "nc_260") (pintype "passive"))
    )
    (net (code "78") (name "Net-(J3-Pad61)") (class "Default")
      (node (ref "J3") (pin "61") (pinfunction "61_61") (pintype "passive"))
      (node (ref "rxPI1") (pin "262") (pinfunction "GND_262") (pintype "passive"))
    )
    (net (code "79") (name "Net-(J3-Pad63)") (class "Default")
      (node (ref "J3") (pin "63") (pinfunction "63_63") (pintype "passive"))
      (node (ref "rxPI1") (pin "264") (pinfunction "nc_264") (pintype "passive"))
    )
    (net (code "80") (name "Net-(J3-Pad65)") (class "Default")
      (node (ref "J3") (pin "65") (pinfunction "65_65") (pintype "passive"))
      (node (ref "rxPI1") (pin "266") (pinfunction "nc_266") (pintype "passive"))
    )
    (net (code "81") (name "Net-(J3-Pad67)") (class "Default")
      (node (ref "J3") (pin "67") (pinfunction "67_67") (pintype "passive"))
      (node (ref "rxPI1") (pin "268") (pinfunction "GND_268") (pintype "passive"))
    )
    (net (code "82") (name "Net-(J3-Pad69)") (class "Default")
      (node (ref "J3") (pin "69") (pinfunction "69_69") (pintype "passive"))
      (node (ref "rxPI1") (pin "270") (pinfunction "nc_270") (pintype "passive"))
    )
    (net (code "83") (name "Net-(J3-Pad71)") (class "Default")
      (node (ref "J3") (pin "71") (pinfunction "71_71") (pintype "passive"))
      (node (ref "rxPI1") (pin "272") (pinfunction "GND_272") (pintype "passive"))
    )
    (net (code "84") (name "Net-(J3-Pad75)") (class "Default")
      (node (ref "J3") (pin "75") (pinfunction "75_75") (pintype "passive"))
      (node (ref "rxPI1") (pin "276") (pinfunction "GND_276") (pintype "passive"))
    )
    (net (code "85") (name "Net-(J3-Pad77)") (class "Default")
      (node (ref "J3") (pin "77") (pinfunction "77_77") (pintype "passive"))
      (node (ref "rxPI1") (pin "278") (pinfunction "nc_278") (pintype "passive"))
    )
    (net (code "86") (name "Net-(J3-Pad79)") (class "Default")
      (node (ref "J3") (pin "79") (pinfunction "79_79") (pintype "passive"))
      (node (ref "rxPI1") (pin "280") (pinfunction "nc_280") (pintype "passive"))
    )
    (net (code "87") (name "Net-(J3-Pad81)") (class "Default")
      (node (ref "J3") (pin "81") (pinfunction "81_81") (pintype "passive"))
      (node (ref "rxPI1") (pin "282") (pinfunction "nc_282") (pintype "passive"))
    )
    (net (code "88") (name "Net-(J3-Pad83)") (class "Default")
      (node (ref "J3") (pin "83") (pinfunction "83_83") (pintype "passive"))
      (node (ref "rxPI1") (pin "284") (pinfunction "nc_284") (pintype "passive"))
    )
    (net (code "89") (name "Net-(J3-Pad85)") (class "Default")
      (node (ref "J3") (pin "85") (pinfunction "85_85") (pintype "passive"))
      (node (ref "rxPI1") (pin "286") (pinfunction "nc_286") (pintype "passive"))
    )
    (net (code "90") (name "Net-(J3-Pad87)") (class "Default")
      (node (ref "J3") (pin "87") (pinfunction "87_87") (pintype "passive"))
      (node (ref "rxPI1") (pin "288") (pinfunction "nc_288") (pintype "passive"))
    )
    (net (code "91") (name "Net-(J3-Pad89)") (class "Default")
      (node (ref "J3") (pin "89") (pinfunction "89_89") (pintype "passive"))
      (node (ref "rxPI1") (pin "290") (pinfunction "nc_290") (pintype "passive"))
    )
    (net (code "92") (name "Net-(J3-Pad92)") (class "Default")
      (node (ref "J3") (pin "92") (pinfunction "92_92") (pintype "passive"))
      (node (ref "rxPI1") (pin "291") (pinfunction "nc_291") (pintype "passive"))
    )
    (net (code "93") (name "Net-(J3-Pad99)") (class "Default")
      (node (ref "J3") (pin "99") (pinfunction "99_99") (pintype "passive"))
      (node (ref "rxPI1") (pin "300") (pinfunction "GND_300") (pintype "passive"))
    )
    (net (code "94") (name "Net-(J6-LED1)") (class "Default")
      (node (ref "J6") (pin "10") (pinfunction "LED1_10") (pintype "passive"))
      (node (ref "LED1") (pin "1") (pinfunction "Cathode_1") (pintype "passive"))
      (node (ref "M.1") (pin "10") (pinfunction "LED1_10") (pintype "passive"))
    )
    (net (code "95") (name "Net-(J6-MFG_CLK)") (class "Default")
      (node (ref "J6") (pin "58") (pinfunction "MFG_CLK_58") (pintype "passive"))
      (node (ref "M.1") (pin "58") (pinfunction "MFG_CLK_58") (pintype "passive"))
    )
    (net (code "96") (name "Net-(J6-MFG_D)") (class "Default")
      (node (ref "J6") (pin "56") (pinfunction "MFG_D_56") (pintype "passive"))
      (node (ref "M.1") (pin "56") (pinfunction "MFG_D_56") (pintype "passive"))
    )
    (net (code "97") (name "Net-(J6-N{slash}C-Pad6)") (class "Default")
      (node (ref "J6") (pin "6") (pinfunction "N/C_6") (pintype "passive"))
      (node (ref "M.1") (pin "6") (pinfunction "N/C_6") (pintype "passive"))
    )
    (net (code "98") (name "Net-(J6-N{slash}C-Pad8)") (class "Default")
      (node (ref "J6") (pin "8") (pinfunction "N/C_8") (pintype "passive"))
      (node (ref "M.1") (pin "8") (pinfunction "N/C_8") (pintype "passive"))
    )
    (net (code "99") (name "Net-(J6-N{slash}C-Pad20)") (class "Default")
      (node (ref "J6") (pin "20") (pinfunction "N/C_20") (pintype "passive"))
      (node (ref "M.1") (pin "20") (pinfunction "N/C_20") (pintype "passive"))
    )
    (net (code "100") (name "Net-(J6-N{slash}C-Pad22)") (class "Default")
      (node (ref "J6") (pin "22") (pinfunction "N/C_22") (pintype "passive"))
      (node (ref "M.1") (pin "22") (pinfunction "N/C_22") (pintype "passive"))
    )
    (net (code "101") (name "Net-(J6-N{slash}C-Pad24)") (class "Default")
      (node (ref "J6") (pin "24") (pinfunction "N/C_24") (pintype "passive"))
      (node (ref "M.1") (pin "24") (pinfunction "N/C_24") (pintype "passive"))
    )
    (net (code "102") (name "Net-(J6-N{slash}C-Pad26)") (class "Default")
      (node (ref "J6") (pin "26") (pinfunction "N/C_26") (pintype "passive"))
      (node (ref "M.1") (pin "26") (pinfunction "N/C_26") (pintype "passive"))
    )
    (net (code "103") (name "Net-(J6-N{slash}C-Pad28)") (class "Default")
      (node (ref "J6") (pin "28") (pinfunction "N/C_28") (pintype "passive"))
      (node (ref "M.1") (pin "28") (pinfunction "N/C_28") (pintype "passive"))
    )
    (net (code "104") (name "Net-(J6-N{slash}C-Pad30)") (class "Default")
      (node (ref "J6") (pin "30") (pinfunction "N/C_30") (pintype "passive"))
      (node (ref "M.1") (pin "30") (pinfunction "N/C_30") (pintype "passive"))
    )
    (net (code "105") (name "Net-(J6-N{slash}C-Pad32)") (class "Default")
      (node (ref "J6") (pin "32") (pinfunction "N/C_32") (pintype "passive"))
      (node (ref "M.1") (pin "32") (pinfunction "N/C_32") (pintype "passive"))
    )
    (net (code "106") (name "Net-(J6-N{slash}C-Pad34)") (class "Default")
      (node (ref "J6") (pin "34") (pinfunction "N/C_34") (pintype "passive"))
      (node (ref "M.1") (pin "34") (pinfunction "N/C_34") (pintype "passive"))
    )
    (net (code "107") (name "Net-(J6-N{slash}C-Pad36)") (class "Default")
      (node (ref "J6") (pin "36") (pinfunction "N/C_36") (pintype "passive"))
      (node (ref "M.1") (pin "36") (pinfunction "N/C_36") (pintype "passive"))
    )
    (net (code "108") (name "Net-(J6-N{slash}C-Pad38)") (class "Default")
      (node (ref "J6") (pin "38") (pinfunction "N/C_38") (pintype "passive"))
      (node (ref "M.1") (pin "38") (pinfunction "N/C_38") (pintype "passive"))
    )
    (net (code "109") (name "Net-(J6-N{slash}C-Pad40)") (class "Default")
      (node (ref "J6") (pin "40") (pinfunction "N/C_40") (pintype "passive"))
      (node (ref "M.1") (pin "40") (pinfunction "N/C_40") (pintype "passive"))
    )
    (net (code "110") (name "Net-(J6-N{slash}C-Pad42)") (class "Default")
      (node (ref "J6") (pin "42") (pinfunction "N/C_42") (pintype "passive"))
      (node (ref "M.1") (pin "42") (pinfunction "N/C_42") (pintype "passive"))
    )
    (net (code "111") (name "Net-(J6-N{slash}C-Pad44)") (class "Default")
      (node (ref "J6") (pin "44") (pinfunction "N/C_44") (pintype "passive"))
      (node (ref "M.1") (pin "44") (pinfunction "N/C_44") (pintype "passive"))
    )
    (net (code "112") (name "Net-(J6-N{slash}C-Pad46)") (class "Default")
      (node (ref "J6") (pin "46") (pinfunction "N/C_46") (pintype "passive"))
      (node (ref "M.1") (pin "46") (pinfunction "N/C_46") (pintype "passive"))
    )
    (net (code "113") (name "Net-(J6-N{slash}C-Pad48)") (class "Default")
      (node (ref "J6") (pin "48") (pinfunction "N/C_48") (pintype "passive"))
      (node (ref "M.1") (pin "48") (pinfunction "N/C_48") (pintype "passive"))
    )
    (net (code "114") (name "Net-(J6-N{slash}C-Pad67)") (class "Default")
      (node (ref "J6") (pin "67") (pinfunction "N/C_67") (pintype "passive"))
      (node (ref "M.1") (pin "67") (pinfunction "N/C_67") (pintype "passive"))
    )
    (net (code "115") (name "Net-(J6-PEDET)") (class "Default")
      (node (ref "J6") (pin "69") (pinfunction "PEDET_69") (pintype "passive"))
      (node (ref "M.1") (pin "69") (pinfunction "PEDET_69") (pintype "passive"))
    )
    (net (code "116") (name "Net-(J6-PERn1)") (class "Default")
      (node (ref "J6") (pin "35") (pinfunction "PERn1_35") (pintype "passive"))
      (node (ref "M.1") (pin "35") (pinfunction "PERn1_35") (pintype "passive"))
    )
    (net (code "117") (name "Net-(J6-PERn2)") (class "Default")
      (node (ref "J6") (pin "23") (pinfunction "PERn2_23") (pintype "passive"))
      (node (ref "M.1") (pin "23") (pinfunction "PERn2_23") (pintype "passive"))
    )
    (net (code "118") (name "Net-(J6-PERn3)") (class "Default")
      (node (ref "J6") (pin "11") (pinfunction "PERn3_11") (pintype "passive"))
      (node (ref "M.1") (pin "11") (pinfunction "PERn3_11") (pintype "passive"))
    )
    (net (code "119") (name "Net-(J6-PERp1)") (class "Default")
      (node (ref "J6") (pin "37") (pinfunction "PERp1_37") (pintype "passive"))
      (node (ref "M.1") (pin "37") (pinfunction "PERp1_37") (pintype "passive"))
    )
    (net (code "120") (name "Net-(J6-PERp2)") (class "Default")
      (node (ref "J6") (pin "25") (pinfunction "PERp2_25") (pintype "passive"))
      (node (ref "M.1") (pin "25") (pinfunction "PERp2_25") (pintype "passive"))
    )
    (net (code "121") (name "Net-(J6-PERp3)") (class "Default")
      (node (ref "J6") (pin "13") (pinfunction "PERp3_13") (pintype "passive"))
      (node (ref "M.1") (pin "13") (pinfunction "PERp3_13") (pintype "passive"))
    )
    (net (code "122") (name "Net-(J6-PETn1)") (class "Default")
      (node (ref "J6") (pin "29") (pinfunction "PETn1_29") (pintype "passive"))
      (node (ref "M.1") (pin "29") (pinfunction "PETn1_29") (pintype "passive"))
    )
    (net (code "123") (name "Net-(J6-PETn2)") (class "Default")
      (node (ref "J6") (pin "17") (pinfunction "PETn2_17") (pintype "passive"))
      (node (ref "M.1") (pin "17") (pinfunction "PETn2_17") (pintype "passive"))
    )
    (net (code "124") (name "Net-(J6-PETn3)") (class "Default")
      (node (ref "J6") (pin "5") (pinfunction "PETn3_5") (pintype "passive"))
      (node (ref "M.1") (pin "5") (pinfunction "PETn3_5") (pintype "passive"))
    )
    (net (code "125") (name "Net-(J6-PETp1)") (class "Default")
      (node (ref "J6") (pin "31") (pinfunction "PETp1_31") (pintype "passive"))
      (node (ref "M.1") (pin "31") (pinfunction "PETp1_31") (pintype "passive"))
    )
    (net (code "126") (name "Net-(J6-PETp2)") (class "Default")
      (node (ref "J6") (pin "19") (pinfunction "PETp2_19") (pintype "passive"))
      (node (ref "M.1") (pin "19") (pinfunction "PETp2_19") (pintype "passive"))
    )
    (net (code "127") (name "Net-(J6-PETp3)") (class "Default")
      (node (ref "J6") (pin "7") (pinfunction "PETp3_7") (pintype "passive"))
      (node (ref "M.1") (pin "7") (pinfunction "PETp3_7") (pintype "passive"))
    )
    (net (code "128") (name "Net-(J6-SUSCLK)") (class "Default")
      (node (ref "J6") (pin "68") (pinfunction "SUSCLK_68") (pintype "passive"))
      (node (ref "M.1") (pin "68") (pinfunction "SUSCLK_68") (pintype "passive"))
    )
    (net (code "129") (name "Net-(LED1-Anode)") (class "Default")
      (node (ref "LED1") (pin "2") (pinfunction "Anode_2") (pintype "passive"))
      (node (ref "R1") (pin "1") (pinfunction "1_1") (pintype "passive"))
    )
    (net (code "130") (name "Net-(rPI1A-BT_nDisable)") (class "Default")
      (node (ref "J1") (pin "92") (pinfunction "92_92") (pintype "passive"))
      (node (ref "J4") (pin "91") (pinfunction "91_91") (pintype "passive"))
      (node (ref "rPI1") (pin "91") (pinfunction "BT_nDisable_91") (pintype "passive"))
      (node (ref "rxPI1") (pin "91") (pinfunction "BT_nDisable_91") (pintype "passive"))
    )
    (net (code "131") (name "Net-(rPI1A-CAM_GPIO1)") (class "Default")
      (node (ref "J1") (pin "99") (pinfunction "99_99") (pintype "passive"))
      (node (ref "J4") (pin "100") (pinfunction "100_100") (pintype "passive"))
      (node (ref "rPI1") (pin "100") (pinfunction "CAM_GPIO1_100") (pintype "passive"))
      (node (ref "rxPI1") (pin "100") (pinfunction "CAM_GPIO1_100") (pintype "passive"))
    )
    (net (code "132") (name "Net-(rPI1A-CC1)") (class "Default")
      (node (ref "J1") (pin "93") (pinfunction "93_93") (pintype "passive"))
      (node (ref "J4") (pin "94") (pinfunction "94_94") (pintype "passive"))
      (node (ref "rPI1") (pin "94") (pinfunction "CC1_94") (pintype "passive"))
      (node (ref "rxPI1") (pin "94") (pinfunction "CC1_94") (pintype "passive"))
    )
    (net (code "133") (name "Net-(rPI1A-CC2)") (class "Default")
      (node (ref "J1") (pin "95") (pinfunction "95_95") (pintype "passive"))
      (node (ref "J4") (pin "96") (pinfunction "96_96") (pintype "passive"))
      (node (ref "rPI1") (pin "96") (pinfunction "CC2_96") (pintype "passive"))
      (node (ref "rxPI1") (pin "96") (pinfunction "CC2_96") (pintype "passive"))
    )
    (net (code "134") (name "Net-(rPI1A-EEPROM_nWP)") (class "Default")
      (node (ref "J1") (pin "19") (pinfunction "19_19") (pintype "passive"))
      (node (ref "J4") (pin "20") (pinfunction "20_20") (pintype "passive"))
      (node (ref "rPI1") (pin "20") (pinfunction "EEPROM_nWP_20") (pintype "passive"))
      (node (ref "rxPI1") (pin "20") (pinfunction "EEPROM_nWP_20") (pintype "passive"))
    )
    (net (code "135") (name "Net-(rPI1A-Ethernet_Pair0_N)") (class "Default")
      (node (ref "J1") (pin "9") (pinfunction "9_9") (pintype "passive"))
      (node (ref "J4") (pin "10") (pinfunction "10_10") (pintype "passive"))
      (node (ref "rPI1") (pin "10") (pinfunction "Ethernet_Pair0_N_10") (pintype "passive"))
      (node (ref "rxPI1") (pin "10") (pinfunction "Ethernet_Pair0_N_10") (pintype "passive"))
    )
    (net (code "136") (name "Net-(rPI1A-Ethernet_Pair0_P)") (class "Default")
      (node (ref "J1") (pin "11") (pinfunction "11_11") (pintype "passive"))
      (node (ref "J4") (pin "12") (pinfunction "12_12") (pintype "passive"))
      (node (ref "rPI1") (pin "12") (pinfunction "Ethernet_Pair0_P_12") (pintype "passive"))
      (node (ref "rxPI1") (pin "12") (pinfunction "Ethernet_Pair0_P_12") (pintype "passive"))
    )
    (net (code "137") (name "Net-(rPI1A-Ethernet_Pair1_N)") (class "Default")
      (node (ref "J1") (pin "5") (pinfunction "5_5") (pintype "passive"))
      (node (ref "J4") (pin "6") (pinfunction "6_6") (pintype "passive"))
      (node (ref "rPI1") (pin "6") (pinfunction "Ethernet_Pair1_N_6") (pintype "passive"))
      (node (ref "rxPI1") (pin "6") (pinfunction "Ethernet_Pair1_N_6") (pintype "passive"))
    )
    (net (code "138") (name "Net-(rPI1A-Ethernet_Pair1_P)") (class "Default")
      (node (ref "J1") (pin "3") (pinfunction "3_3") (pintype "passive"))
      (node (ref "J4") (pin "4") (pinfunction "4_4") (pintype "passive"))
      (node (ref "rPI1") (pin "4") (pinfunction "Ethernet_Pair1_P_4") (pintype "passive"))
      (node (ref "rxPI1") (pin "4") (pinfunction "Ethernet_Pair1_P_4") (pintype "passive"))
    )
    (net (code "139") (name "Net-(rPI1A-Ethernet_Pair2_N)") (class "Default")
      (node (ref "J1") (pin "10") (pinfunction "10_10") (pintype "passive"))
      (node (ref "J4") (pin "9") (pinfunction "9_9") (pintype "passive"))
      (node (ref "rPI1") (pin "9") (pinfunction "Ethernet_Pair2_N_9") (pintype "passive"))
      (node (ref "rxPI1") (pin "9") (pinfunction "Ethernet_Pair2_N_9") (pintype "passive"))
    )
    (net (code "140") (name "Net-(rPI1A-Ethernet_Pair2_P)") (class "Default")
      (node (ref "J1") (pin "12") (pinfunction "12_12") (pintype "passive"))
      (node (ref "J4") (pin "11") (pinfunction "11_11") (pintype "passive"))
      (node (ref "rPI1") (pin "11") (pinfunction "Ethernet_Pair2_P_11") (pintype "passive"))
      (node (ref "rxPI1") (pin "11") (pinfunction "Ethernet_Pair2_P_11") (pintype "passive"))
    )
    (net (code "141") (name "Net-(rPI1A-Ethernet_Pair3_N)") (class "Default")
      (node (ref "J1") (pin "6") (pinfunction "6_6") (pintype "passive"))
      (node (ref "J4") (pin "5") (pinfunction "5_5") (pintype "passive"))
      (node (ref "rPI1") (pin "5") (pinfunction "Ethernet_Pair3_N_5") (pintype "passive"))
      (node (ref "rxPI1") (pin "5") (pinfunction "Ethernet_Pair3_N_5") (pintype "passive"))
    )
    (net (code "142") (name "Net-(rPI1A-Ethernet_Pair3_P)") (class "Default")
      (node (ref "J1") (pin "4") (pinfunction "4_4") (pintype "passive"))
      (node (ref "J4") (pin "3") (pinfunction "3_3") (pintype "passive"))
      (node (ref "rPI1") (pin "3") (pinfunction "Ethernet_Pair3_P_3") (pintype "passive"))
      (node (ref "rxPI1") (pin "3") (pinfunction "Ethernet_Pair3_P_3") (pintype "passive"))
    )
    (net (code "143") (name "Net-(rPI1A-Ethernet_SYNC_IN(1.8v))") (class "Default")
      (node (ref "J1") (pin "15") (pinfunction "15_15") (pintype "passive"))
      (node (ref "J4") (pin "16") (pinfunction "16_16") (pintype "passive"))
      (node (ref "rPI1") (pin "16") (pinfunction "Ethernet_SYNC_IN(1.8v)_16") (pintype "passive"))
      (node (ref "rxPI1") (pin "16") (pinfunction "Ethernet_SYNC_IN(1.8v)_16") (pintype "passive"))
    )
    (net (code "144") (name "Net-(rPI1A-Ethernet_SYNC_OUT(1.8v))") (class "Default")
      (node (ref "J1") (pin "17") (pinfunction "17_17") (pintype "passive"))
      (node (ref "J4") (pin "18") (pinfunction "18_18") (pintype "passive"))
      (node (ref "rPI1") (pin "18") (pinfunction "Ethernet_SYNC_OUT(1.8v)_18") (pintype "passive"))
      (node (ref "rxPI1") (pin "18") (pinfunction "Ethernet_SYNC_OUT(1.8v)_18") (pintype "passive"))
    )
    (net (code "145") (name "Net-(rPI1A-Ethernet_nLED2(3.3v))") (class "Default")
      (node (ref "J1") (pin "18") (pinfunction "18_18") (pintype "passive"))
      (node (ref "J4") (pin "17") (pinfunction "17_17") (pintype "passive"))
      (node (ref "rPI1") (pin "17") (pinfunction "Ethernet_nLED2(3.3v)_17") (pintype "passive"))
      (node (ref "rxPI1") (pin "17") (pinfunction "Ethernet_nLED2(3.3v)_17") (pintype "passive"))
    )
    (net (code "146") (name "Net-(rPI1A-Ethernet_nLED3(3.3v))") (class "Default")
      (node (ref "J1") (pin "16") (pinfunction "16_16") (pintype "passive"))
      (node (ref "J4") (pin "15") (pinfunction "15_15") (pintype "passive"))
      (node (ref "rPI1") (pin "15") (pinfunction "Ethernet_nLED3(3.3v)_15") (pintype "passive"))
      (node (ref "rxPI1") (pin "15") (pinfunction "Ethernet_nLED3(3.3v)_15") (pintype "passive"))
    )
    (net (code "147") (name "Net-(rPI1A-FAN_PWM)") (class "Default")
      (node (ref "J1") (pin "20") (pinfunction "20_20") (pintype "passive"))
      (node (ref "J4") (pin "19") (pinfunction "19_19") (pintype "passive"))
      (node (ref "rPI1") (pin "19") (pinfunction "FAN_PWM_19") (pintype "passive"))
      (node (ref "rxPI1") (pin "19") (pinfunction "FAN_PWM_19") (pintype "passive"))
    )
    (net (code "148") (name "Net-(rPI1A-GPIO2)") (class "Default")
      (node (ref "J1") (pin "57") (pinfunction "57_57") (pintype "passive"))
      (node (ref "J4") (pin "58") (pinfunction "58_58") (pintype "passive"))
      (node (ref "rPI1") (pin "58") (pinfunction "GPIO2_58") (pintype "passive"))
      (node (ref "rxPI1") (pin "58") (pinfunction "GPIO2_58") (pintype "passive"))
    )
    (net (code "149") (name "Net-(rPI1A-GPIO3)") (class "Default")
      (node (ref "J1") (pin "55") (pinfunction "55_55") (pintype "passive"))
      (node (ref "J4") (pin "56") (pinfunction "56_56") (pintype "passive"))
      (node (ref "rPI1") (pin "56") (pinfunction "GPIO3_56") (pintype "passive"))
      (node (ref "rxPI1") (pin "56") (pinfunction "GPIO3_56") (pintype "passive"))
    )
    (net (code "150") (name "Net-(rPI1A-GPIO4)") (class "Default")
      (node (ref "J1") (pin "53") (pinfunction "53_53") (pintype "passive"))
      (node (ref "J4") (pin "54") (pinfunction "54_54") (pintype "passive"))
      (node (ref "rPI1") (pin "54") (pinfunction "GPIO4_54") (pintype "passive"))
      (node (ref "rxPI1") (pin "54") (pinfunction "GPIO4_54") (pintype "passive"))
    )
    (net (code "151") (name "Net-(rPI1A-GPIO5)") (class "Default")
      (node (ref "J1") (pin "33") (pinfunction "33_33") (pintype "passive"))
      (node (ref "J4") (pin "34") (pinfunction "34_34") (pintype "passive"))
      (node (ref "rPI1") (pin "34") (pinfunction "GPIO5_34") (pintype "passive"))
      (node (ref "rxPI1") (pin "34") (pinfunction "GPIO5_34") (pintype "passive"))
    )
    (net (code "152") (name "Net-(rPI1A-GPIO6)") (class "Default")
      (node (ref "J1") (pin "29") (pinfunction "29_29") (pintype "passive"))
      (node (ref "J4") (pin "30") (pinfunction "30_30") (pintype "passive"))
      (node (ref "rPI1") (pin "30") (pinfunction "GPIO6_30") (pintype "passive"))
      (node (ref "rxPI1") (pin "30") (pinfunction "GPIO6_30") (pintype "passive"))
    )
    (net (code "153") (name "Net-(rPI1A-GPIO7)") (class "Default")
      (node (ref "J1") (pin "38") (pinfunction "38_38") (pintype "passive"))
      (node (ref "J4") (pin "37") (pinfunction "37_37") (pintype "passive"))
      (node (ref "rPI1") (pin "37") (pinfunction "GPIO7_37") (pintype "passive"))
      (node (ref "rxPI1") (pin "37") (pinfunction "GPIO7_37") (pintype "passive"))
    )
    (net (code "154") (name "Net-(rPI1A-GPIO8)") (class "Default")
      (node (ref "J1") (pin "40") (pinfunction "40_40") (pintype "passive"))
      (node (ref "J4") (pin "39") (pinfunction "39_39") (pintype "passive"))
      (node (ref "rPI1") (pin "39") (pinfunction "GPIO8_39") (pintype "passive"))
      (node (ref "rxPI1") (pin "39") (pinfunction "GPIO8_39") (pintype "passive"))
    )
    (net (code "155") (name "Net-(rPI1A-GPIO9)") (class "Default")
      (node (ref "J1") (pin "39") (pinfunction "39_39") (pintype "passive"))
      (node (ref "J4") (pin "40") (pinfunction "40_40") (pintype "passive"))
      (node (ref "rPI1") (pin "40") (pinfunction "GPIO9_40") (pintype "passive"))
      (node (ref "rxPI1") (pin "40") (pinfunction "GPIO9_40") (pintype "passive"))
    )
    (net (code "156") (name "Net-(rPI1A-GPIO10)") (class "Default")
      (node (ref "J1") (pin "43") (pinfunction "43_43") (pintype "passive"))
      (node (ref "J4") (pin "44") (pinfunction "44_44") (pintype "passive"))
      (node (ref "rPI1") (pin "44") (pinfunction "GPIO10_44") (pintype "passive"))
      (node (ref "rxPI1") (pin "44") (pinfunction "GPIO10_44") (pintype "passive"))
    )
    (net (code "157") (name "Net-(rPI1A-GPIO11)") (class "Default")
      (node (ref "J1") (pin "37") (pinfunction "37_37") (pintype "passive"))
      (node (ref "J4") (pin "38") (pinfunction "38_38") (pintype "passive"))
      (node (ref "rPI1") (pin "38") (pinfunction "GPIO11_38") (pintype "passive"))
      (node (ref "rxPI1") (pin "38") (pinfunction "GPIO11_38") (pintype "passive"))
    )
    (net (code "158") (name "Net-(rPI1A-GPIO12)") (class "Default")
      (node (ref "J1") (pin "32") (pinfunction "32_32") (pintype "passive"))
      (node (ref "J4") (pin "31") (pinfunction "31_31") (pintype "passive"))
      (node (ref "rPI1") (pin "31") (pinfunction "GPIO12_31") (pintype "passive"))
      (node (ref "rxPI1") (pin "31") (pinfunction "GPIO12_31") (pintype "passive"))
    )
    (net (code "159") (name "Net-(rPI1A-GPIO13)") (class "Default")
      (node (ref "J1") (pin "27") (pinfunction "27_27") (pintype "passive"))
      (node (ref "J4") (pin "28") (pinfunction "28_28") (pintype "passive"))
      (node (ref "rPI1") (pin "28") (pinfunction "GPIO13_28") (pintype "passive"))
      (node (ref "rxPI1") (pin "28") (pinfunction "GPIO13_28") (pintype "passive"))
    )
    (net (code "160") (name "Net-(rPI1A-GPIO14)") (class "Default")
      (node (ref "J1") (pin "56") (pinfunction "56_56") (pintype "passive"))
      (node (ref "J4") (pin "55") (pinfunction "55_55") (pintype "passive"))
      (node (ref "rPI1") (pin "55") (pinfunction "GPIO14_55") (pintype "passive"))
      (node (ref "rxPI1") (pin "55") (pinfunction "GPIO14_55") (pintype "passive"))
    )
    (net (code "161") (name "Net-(rPI1A-GPIO15)") (class "Default")
      (node (ref "J1") (pin "52") (pinfunction "52_52") (pintype "passive"))
      (node (ref "J4") (pin "51") (pinfunction "51_51") (pintype "passive"))
      (node (ref "rPI1") (pin "51") (pinfunction "GPIO15_51") (pintype "passive"))
      (node (ref "rxPI1") (pin "51") (pinfunction "GPIO15_51") (pintype "passive"))
    )
    (net (code "162") (name "Net-(rPI1A-GPIO16)") (class "Default")
      (node (ref "J1") (pin "30") (pinfunction "30_30") (pintype "passive"))
      (node (ref "J4") (pin "29") (pinfunction "29_29") (pintype "passive"))
      (node (ref "rPI1") (pin "29") (pinfunction "GPIO16_29") (pintype "passive"))
      (node (ref "rxPI1") (pin "29") (pinfunction "GPIO16_29") (pintype "passive"))
    )
    (net (code "163") (name "Net-(rPI1A-GPIO17)") (class "Default")
      (node (ref "J1") (pin "49") (pinfunction "49_49") (pintype "passive"))
      (node (ref "J4") (pin "50") (pinfunction "50_50") (pintype "passive"))
      (node (ref "rPI1") (pin "50") (pinfunction "GPIO17_50") (pintype "passive"))
      (node (ref "rxPI1") (pin "50") (pinfunction "GPIO17_50") (pintype "passive"))
    )
    (net (code "164") (name "Net-(rPI1A-GPIO18)") (class "Default")
      (node (ref "J1") (pin "50") (pinfunction "50_50") (pintype "passive"))
      (node (ref "J4") (pin "49") (pinfunction "49_49") (pintype "passive"))
      (node (ref "rPI1") (pin "49") (pinfunction "GPIO18_49") (pintype "passive"))
      (node (ref "rxPI1") (pin "49") (pinfunction "GPIO18_49") (pintype "passive"))
    )
    (net (code "165") (name "Net-(rPI1A-GPIO19)") (class "Default")
      (node (ref "J1") (pin "25") (pinfunction "25_25") (pintype "passive"))
      (node (ref "J4") (pin "26") (pinfunction "26_26") (pintype "passive"))
      (node (ref "rPI1") (pin "26") (pinfunction "GPIO19_26") (pintype "passive"))
      (node (ref "rxPI1") (pin "26") (pinfunction "GPIO19_26") (pintype "passive"))
    )
    (net (code "166") (name "Net-(rPI1A-GPIO21)") (class "Default")
      (node (ref "J1") (pin "26") (pinfunction "26_26") (pintype "passive"))
      (node (ref "J4") (pin "25") (pinfunction "25_25") (pintype "passive"))
      (node (ref "rPI1") (pin "25") (pinfunction "GPIO21_25") (pintype "passive"))
      (node (ref "rxPI1") (pin "25") (pinfunction "GPIO21_25") (pintype "passive"))
    )
    (net (code "167") (name "Net-(rPI1A-GPIO22)") (class "Default")
      (node (ref "J1") (pin "45") (pinfunction "45_45") (pintype "passive"))
      (node (ref "J4") (pin "46") (pinfunction "46_46") (pintype "passive"))
      (node (ref "rPI1") (pin "46") (pinfunction "GPIO22_46") (pintype "passive"))
      (node (ref "rxPI1") (pin "46") (pinfunction "GPIO22_46") (pintype "passive"))
    )
    (net (code "168") (name "Net-(rPI1A-GPIO24)") (class "Default")
      (node (ref "J1") (pin "46") (pinfunction "46_46") (pintype "passive"))
      (node (ref "J4") (pin "45") (pinfunction "45_45") (pintype "passive"))
      (node (ref "rPI1") (pin "45") (pinfunction "GPIO24_45") (pintype "passive"))
      (node (ref "rxPI1") (pin "45") (pinfunction "GPIO24_45") (pintype "passive"))
    )
    (net (code "169") (name "Net-(rPI1A-GPIO25)") (class "Default")
      (node (ref "J1") (pin "42") (pinfunction "42_42") (pintype "passive"))
      (node (ref "J4") (pin "41") (pinfunction "41_41") (pintype "passive"))
      (node (ref "rPI1") (pin "41") (pinfunction "GPIO25_41") (pintype "passive"))
      (node (ref "rxPI1") (pin "41") (pinfunction "GPIO25_41") (pintype "passive"))
    )
    (net (code "170") (name "Net-(rPI1A-GPIO26)") (class "Default")
      (node (ref "J1") (pin "23") (pinfunction "23_23") (pintype "passive"))
      (node (ref "J4") (pin "24") (pinfunction "24_24") (pintype "passive"))
      (node (ref "rPI1") (pin "24") (pinfunction "GPIO26_24") (pintype "passive"))
      (node (ref "rxPI1") (pin "24") (pinfunction "GPIO26_24") (pintype "passive"))
    )
    (net (code "171") (name "Net-(rPI1A-GPIO27)") (class "Default")
      (node (ref "J1") (pin "47") (pinfunction "47_47") (pintype "passive"))
      (node (ref "J4") (pin "48") (pinfunction "48_48") (pintype "passive"))
      (node (ref "rPI1") (pin "48") (pinfunction "GPIO27_48") (pintype "passive"))
      (node (ref "rxPI1") (pin "48") (pinfunction "GPIO27_48") (pintype "passive"))
    )
    (net (code "172") (name "Net-(rPI1A-GPIO_VREF(1.8v{slash}3.3v_Input))") (class "Default")
      (node (ref "J1") (pin "77") (pinfunction "77_77") (pintype "passive"))
      (node (ref "J4") (pin "78") (pinfunction "78_78") (pintype "passive"))
      (node (ref "rPI1") (pin "78") (pinfunction "GPIO_VREF(1.8v/3.3v_Input)_78") (pintype "passive"))
      (node (ref "rxPI1") (pin "78") (pinfunction "GPIO_VREF(1.8v/3.3v_Input)_78") (pintype "passive"))
    )
    (net (code "173") (name "Net-(rPI1A-Global_EN)") (class "Default")
      (node (ref "J1") (pin "100") (pinfunction "100_100") (pintype "passive"))
      (node (ref "J4") (pin "99") (pinfunction "99_99") (pintype "passive"))
      (node (ref "rPI1") (pin "99") (pinfunction "Global_EN_99") (pintype "passive"))
      (node (ref "rxPI1") (pin "99") (pinfunction "Global_EN_99") (pintype "passive"))
    )
    (net (code "174") (name "Net-(rPI1A-ID_SC)") (class "Default")
      (node (ref "J1") (pin "36") (pinfunction "36_36") (pintype "passive"))
      (node (ref "J4") (pin "35") (pinfunction "35_35") (pintype "passive"))
      (node (ref "rPI1") (pin "35") (pinfunction "ID_SC_35") (pintype "passive"))
      (node (ref "rxPI1") (pin "35") (pinfunction "ID_SC_35") (pintype "passive"))
    )
    (net (code "175") (name "Net-(rPI1A-ID_SD)") (class "Default")
      (node (ref "J1") (pin "35") (pinfunction "35_35") (pintype "passive"))
      (node (ref "J4") (pin "36") (pinfunction "36_36") (pintype "passive"))
      (node (ref "rPI1") (pin "36") (pinfunction "ID_SD_36") (pintype "passive"))
      (node (ref "rxPI1") (pin "36") (pinfunction "ID_SD_36") (pintype "passive"))
    )
    (net (code "176") (name "Net-(rPI1A-PI_nLED_Activity)") (class "Default")
      (node (ref "J1") (pin "22") (pinfunction "22_22") (pintype "passive"))
      (node (ref "J4") (pin "21") (pinfunction "21_21") (pintype "passive"))
      (node (ref "rPI1") (pin "21") (pinfunction "PI_nLED_Activity_21") (pintype "passive"))
      (node (ref "rxPI1") (pin "21") (pinfunction "PI_nLED_Activity_21") (pintype "passive"))
    )
    (net (code "177") (name "Net-(rPI1A-RUN_PG)") (class "Default")
      (node (ref "J1") (pin "91") (pinfunction "91_91") (pintype "passive"))
      (node (ref "J4") (pin "92") (pinfunction "92_92") (pintype "passive"))
      (node (ref "rPI1") (pin "92") (pinfunction "RUN_PG_92") (pintype "passive"))
      (node (ref "rxPI1") (pin "92") (pinfunction "RUN_PG_92") (pintype "passive"))
    )
    (net (code "178") (name "Net-(rPI1A-Reserved)") (class "Default")
      (node (ref "J1") (pin "75") (pinfunction "75_75") (pintype "passive"))
      (node (ref "J4") (pin "76") (pinfunction "76_76") (pintype "passive"))
      (node (ref "rPI1") (pin "76") (pinfunction "Reserved_76") (pintype "passive"))
      (node (ref "rxPI1") (pin "76") (pinfunction "Reserved_76") (pintype "passive"))
    )
    (net (code "179") (name "Net-(rPI1A-SCL0)") (class "Default")
      (node (ref "J1") (pin "79") (pinfunction "79_79") (pintype "passive"))
      (node (ref "J4") (pin "80") (pinfunction "80_80") (pintype "passive"))
      (node (ref "rPI1") (pin "80") (pinfunction "SCL0_80") (pintype "passive"))
      (node (ref "rxPI1") (pin "80") (pinfunction "SCL0_80") (pintype "passive"))
    )
    (net (code "180") (name "Net-(rPI1A-SDA0)") (class "Default")
      (node (ref "J1") (pin "81") (pinfunction "81_81") (pintype "passive"))
      (node (ref "J4") (pin "82") (pinfunction "82_82") (pintype "passive"))
      (node (ref "rPI1") (pin "82") (pinfunction "SDA0_82") (pintype "passive"))
      (node (ref "rxPI1") (pin "82") (pinfunction "SDA0_82") (pintype "passive"))
    )
    (net (code "181") (name "Net-(rPI1A-SD_CLK)") (class "Default")
      (node (ref "J1") (pin "58") (pinfunction "58_58") (pintype "passive"))
      (node (ref "J4") (pin "57") (pinfunction "57_57") (pintype "passive"))
      (node (ref "rPI1") (pin "57") (pinfunction "SD_CLK_57") (pintype "passive"))
      (node (ref "rxPI1") (pin "57") (pinfunction "SD_CLK_57") (pintype "passive"))
    )
    (net (code "182") (name "Net-(rPI1A-SD_CMD)") (class "Default")
      (node (ref "J1") (pin "61") (pinfunction "61_61") (pintype "passive"))
      (node (ref "J4") (pin "62") (pinfunction "62_62") (pintype "passive"))
      (node (ref "rPI1") (pin "62") (pinfunction "SD_CMD_62") (pintype "passive"))
      (node (ref "rxPI1") (pin "62") (pinfunction "SD_CMD_62") (pintype "passive"))
    )
    (net (code "183") (name "Net-(rPI1A-SD_DAT0)") (class "Default")
      (node (ref "J1") (pin "64") (pinfunction "64_64") (pintype "passive"))
      (node (ref "J4") (pin "63") (pinfunction "63_63") (pintype "passive"))
      (node (ref "rPI1") (pin "63") (pinfunction "SD_DAT0_63") (pintype "passive"))
      (node (ref "rxPI1") (pin "63") (pinfunction "SD_DAT0_63") (pintype "passive"))
    )
    (net (code "184") (name "Net-(rPI1A-SD_DAT1)") (class "Default")
      (node (ref "J1") (pin "68") (pinfunction "68_68") (pintype "passive"))
      (node (ref "J4") (pin "67") (pinfunction "67_67") (pintype "passive"))
      (node (ref "rPI1") (pin "67") (pinfunction "SD_DAT1_67") (pintype "passive"))
      (node (ref "rxPI1") (pin "67") (pinfunction "SD_DAT1_67") (pintype "passive"))
    )
    (net (code "185") (name "Net-(rPI1A-SD_DAT2)") (class "Default")
      (node (ref "J1") (pin "70") (pinfunction "70_70") (pintype "passive"))
      (node (ref "J4") (pin "69") (pinfunction "69_69") (pintype "passive"))
      (node (ref "rPI1") (pin "69") (pinfunction "SD_DAT2_69") (pintype "passive"))
      (node (ref "rxPI1") (pin "69") (pinfunction "SD_DAT2_69") (pintype "passive"))
    )
    (net (code "186") (name "Net-(rPI1A-SD_DAT3)") (class "Default")
      (node (ref "J1") (pin "62") (pinfunction "62_62") (pintype "passive"))
      (node (ref "J4") (pin "61") (pinfunction "61_61") (pintype "passive"))
      (node (ref "rPI1") (pin "61") (pinfunction "SD_DAT3_61") (pintype "passive"))
      (node (ref "rxPI1") (pin "61") (pinfunction "SD_DAT3_61") (pintype "passive"))
    )
    (net (code "187") (name "Net-(rPI1A-SD_DAT4)") (class "Default")
      (node (ref "J1") (pin "67") (pinfunction "67_67") (pintype "passive"))
      (node (ref "J4") (pin "68") (pinfunction "68_68") (pintype "passive"))
      (node (ref "rPI1") (pin "68") (pinfunction "SD_DAT4_68") (pintype "passive"))
      (node (ref "rxPI1") (pin "68") (pinfunction "SD_DAT4_68") (pintype "passive"))
    )
    (net (code "188") (name "Net-(rPI1A-SD_DAT5)") (class "Default")
      (node (ref "J1") (pin "63") (pinfunction "63_63") (pintype "passive"))
      (node (ref "J4") (pin "64") (pinfunction "64_64") (pintype "passive"))
      (node (ref "rPI1") (pin "64") (pinfunction "SD_DAT5_64") (pintype "passive"))
      (node (ref "rxPI1") (pin "64") (pinfunction "SD_DAT5_64") (pintype "passive"))
    )
    (net (code "189") (name "Net-(rPI1A-SD_DAT6)") (class "Default")
      (node (ref "J1") (pin "71") (pinfunction "71_71") (pintype "passive"))
      (node (ref "J4") (pin "72") (pinfunction "72_72") (pintype "passive"))
      (node (ref "rPI1") (pin "72") (pinfunction "SD_DAT6_72") (pintype "passive"))
      (node (ref "rxPI1") (pin "72") (pinfunction "SD_DAT6_72") (pintype "passive"))
    )
    (net (code "190") (name "Net-(rPI1A-SD_DAT7)") (class "Default")
      (node (ref "J1") (pin "69") (pinfunction "69_69") (pintype "passive"))
      (node (ref "J4") (pin "70") (pinfunction "70_70") (pintype "passive"))
      (node (ref "rPI1") (pin "70") (pinfunction "SD_DAT7_70") (pintype "passive"))
      (node (ref "rxPI1") (pin "70") (pinfunction "SD_DAT7_70") (pintype "passive"))
    )
    (net (code "191") (name "Net-(rPI1A-SD_PWR_ON)") (class "Default")
      (node (ref "J1") (pin "76") (pinfunction "76_76") (pintype "passive"))
      (node (ref "J4") (pin "75") (pinfunction "75_75") (pintype "passive"))
      (node (ref "rPI1") (pin "75") (pinfunction "SD_PWR_ON_75") (pintype "passive"))
      (node (ref "rxPI1") (pin "75") (pinfunction "SD_PWR_ON_75") (pintype "passive"))
    )
    (net (code "192") (name "Net-(rPI1A-SD_VDD_Override)") (class "Default")
      (node (ref "J1") (pin "74") (pinfunction "74_74") (pintype "passive"))
      (node (ref "J4") (pin "73") (pinfunction "73_73") (pintype "passive"))
      (node (ref "rPI1") (pin "73") (pinfunction "SD_VDD_Override_73") (pintype "passive"))
      (node (ref "rxPI1") (pin "73") (pinfunction "SD_VDD_Override_73") (pintype "passive"))
    )
    (net (code "193") (name "Net-(rPI1A-WiFi_nDisable)") (class "Default")
      (node (ref "J1") (pin "90") (pinfunction "90_90") (pintype "passive"))
      (node (ref "J4") (pin "89") (pinfunction "89_89") (pintype "passive"))
      (node (ref "rPI1") (pin "89") (pinfunction "WiFi_nDisable_89") (pintype "passive"))
      (node (ref "rxPI1") (pin "89") (pinfunction "WiFi_nDisable_89") (pintype "passive"))
    )
    (net (code "194") (name "Net-(rPI1A-nPI_LED_PWR)") (class "Default")
      (node (ref "J1") (pin "96") (pinfunction "96_96") (pintype "passive"))
      (node (ref "J4") (pin "95") (pinfunction "95_95") (pintype "passive"))
      (node (ref "rPI1") (pin "95") (pinfunction "nPI_LED_PWR_95") (pintype "passive"))
      (node (ref "rxPI1") (pin "95") (pinfunction "nPI_LED_PWR_95") (pintype "passive"))
    )
    (net (code "195") (name "Net-(rPI1A-nRPIBOOT)") (class "Default")
      (node (ref "J1") (pin "94") (pinfunction "94_94") (pintype "passive"))
      (node (ref "J4") (pin "93") (pinfunction "93_93") (pintype "passive"))
      (node (ref "rPI1") (pin "93") (pinfunction "nRPIBOOT_93") (pintype "passive"))
      (node (ref "rxPI1") (pin "93") (pinfunction "nRPIBOOT_93") (pintype "passive"))
    )
    (net (code "196") (name "Net-(rPI1B-HDMI0_CEC)") (class "Default")
      (node (ref "J2") (pin "52") (pinfunction "52_52") (pintype "passive"))
      (node (ref "J5") (pin "51") (pinfunction "51_51") (pintype "passive"))
      (node (ref "rPI1") (pin "151") (pinfunction "HDMI0_CEC_151") (pintype "passive"))
      (node (ref "rxPI1") (pin "151") (pinfunction "HDMI0_CEC_151") (pintype "passive"))
    )
    (net (code "197") (name "Net-(rPI1B-HDMI0_CLK_N)") (class "Default")
      (node (ref "J2") (pin "89") (pinfunction "89_89") (pintype "passive"))
      (node (ref "J5") (pin "90") (pinfunction "90_90") (pintype "passive"))
      (node (ref "rPI1") (pin "190") (pinfunction "HDMI0_CLK_N_190") (pintype "passive"))
      (node (ref "rxPI1") (pin "190") (pinfunction "HDMI0_CLK_N_190") (pintype "passive"))
    )
    (net (code "198") (name "Net-(rPI1B-HDMI0_CLK_P)") (class "Default")
      (node (ref "J2") (pin "87") (pinfunction "87_87") (pintype "passive"))
      (node (ref "J5") (pin "88") (pinfunction "88_88") (pintype "passive"))
      (node (ref "rPI1") (pin "188") (pinfunction "HDMI0_CLK_P_188") (pintype "passive"))
      (node (ref "rxPI1") (pin "188") (pinfunction "HDMI0_CLK_P_188") (pintype "passive"))
    )
    (net (code "199") (name "Net-(rPI1B-HDMI0_HOTPLUG)") (class "Default")
      (node (ref "J2") (pin "54") (pinfunction "54_54") (pintype "passive"))
      (node (ref "J5") (pin "53") (pinfunction "53_53") (pintype "passive"))
      (node (ref "rPI1") (pin "153") (pinfunction "HDMI0_HOTPLUG_153") (pintype "passive"))
      (node (ref "rxPI1") (pin "153") (pinfunction "HDMI0_HOTPLUG_153") (pintype "passive"))
    )
    (net (code "200") (name "Net-(rPI1B-HDMI0_SCL)") (class "Default")
      (node (ref "J2") (pin "99") (pinfunction "99_99") (pintype "passive"))
      (node (ref "J5") (pin "100") (pinfunction "100_100") (pintype "passive"))
      (node (ref "rPI1") (pin "200") (pinfunction "HDMI0_SCL_200") (pintype "passive"))
      (node (ref "rxPI1") (pin "200") (pinfunction "HDMI0_SCL_200") (pintype "passive"))
    )
    (net (code "201") (name "Net-(rPI1B-HDMI0_SDA)") (class "Default")
      (node (ref "J2") (pin "100") (pinfunction "100_100") (pintype "passive"))
      (node (ref "J5") (pin "99") (pinfunction "99_99") (pintype "passive"))
      (node (ref "rPI1") (pin "199") (pinfunction "HDMI0_SDA_199") (pintype "passive"))
      (node (ref "rxPI1") (pin "199") (pinfunction "HDMI0_SDA_199") (pintype "passive"))
    )
    (net (code "202") (name "Net-(rPI1B-HDMI0_TX0_N)") (class "Default")
      (node (ref "J2") (pin "83") (pinfunction "83_83") (pintype "passive"))
      (node (ref "J5") (pin "84") (pinfunction "84_84") (pintype "passive"))
      (node (ref "rPI1") (pin "184") (pinfunction "HDMI0_TX0_N_184") (pintype "passive"))
      (node (ref "rxPI1") (pin "184") (pinfunction "HDMI0_TX0_N_184") (pintype "passive"))
    )
    (net (code "203") (name "Net-(rPI1B-HDMI0_TX0_P)") (class "Default")
      (node (ref "J2") (pin "81") (pinfunction "81_81") (pintype "passive"))
      (node (ref "J5") (pin "82") (pinfunction "82_82") (pintype "passive"))
      (node (ref "rPI1") (pin "182") (pinfunction "HDMI0_TX0_P_182") (pintype "passive"))
      (node (ref "rxPI1") (pin "182") (pinfunction "HDMI0_TX0_P_182") (pintype "passive"))
    )
    (net (code "204") (name "Net-(rPI1B-HDMI0_TX1_N)") (class "Default")
      (node (ref "J2") (pin "77") (pinfunction "77_77") (pintype "passive"))
      (node (ref "J5") (pin "78") (pinfunction "78_78") (pintype "passive"))
      (node (ref "rPI1") (pin "178") (pinfunction "HDMI0_TX1_N_178") (pintype "passive"))
      (node (ref "rxPI1") (pin "178") (pinfunction "HDMI0_TX1_N_178") (pintype "passive"))
    )
    (net (code "205") (name "Net-(rPI1B-HDMI0_TX1_P)") (class "Default")
      (node (ref "J2") (pin "75") (pinfunction "75_75") (pintype "passive"))
      (node (ref "J5") (pin "76") (pinfunction "76_76") (pintype "passive"))
      (node (ref "rPI1") (pin "176") (pinfunction "HDMI0_TX1_P_176") (pintype "passive"))
      (node (ref "rxPI1") (pin "176") (pinfunction "HDMI0_TX1_P_176") (pintype "passive"))
    )
    (net (code "206") (name "Net-(rPI1B-HDMI0_TX2_N)") (class "Default")
      (node (ref "J2") (pin "71") (pinfunction "71_71") (pintype "passive"))
      (node (ref "J5") (pin "72") (pinfunction "72_72") (pintype "passive"))
      (node (ref "rPI1") (pin "172") (pinfunction "HDMI0_TX2_N_172") (pintype "passive"))
      (node (ref "rxPI1") (pin "172") (pinfunction "HDMI0_TX2_N_172") (pintype "passive"))
    )
    (net (code "207") (name "Net-(rPI1B-HDMI0_TX2_P)") (class "Default")
      (node (ref "J2") (pin "69") (pinfunction "69_69") (pintype "passive"))
      (node (ref "J5") (pin "70") (pinfunction "70_70") (pintype "passive"))
      (node (ref "rPI1") (pin "170") (pinfunction "HDMI0_TX2_P_170") (pintype "passive"))
      (node (ref "rxPI1") (pin "170") (pinfunction "HDMI0_TX2_P_170") (pintype "passive"))
    )
    (net (code "208") (name "Net-(rPI1B-HDMI1_CEC)") (class "Default")
      (node (ref "J2") (pin "50") (pinfunction "50_50") (pintype "passive"))
      (node (ref "J5") (pin "49") (pinfunction "49_49") (pintype "passive"))
      (node (ref "rPI1") (pin "149") (pinfunction "HDMI1_CEC_149") (pintype "passive"))
      (node (ref "rxPI1") (pin "149") (pinfunction "HDMI1_CEC_149") (pintype "passive"))
    )
    (net (code "209") (name "Net-(rPI1B-HDMI1_CLK_N)") (class "Default")
      (node (ref "J2") (pin "65") (pinfunction "65_65") (pintype "passive"))
      (node (ref "J5") (pin "66") (pinfunction "66_66") (pintype "passive"))
      (node (ref "rPI1") (pin "166") (pinfunction "HDMI1_CLK_N_166") (pintype "passive"))
      (node (ref "rxPI1") (pin "166") (pinfunction "HDMI1_CLK_N_166") (pintype "passive"))
    )
    (net (code "210") (name "Net-(rPI1B-HDMI1_CLK_P)") (class "Default")
      (node (ref "J2") (pin "63") (pinfunction "63_63") (pintype "passive"))
      (node (ref "J5") (pin "64") (pinfunction "64_64") (pintype "passive"))
      (node (ref "rPI1") (pin "164") (pinfunction "HDMI1_CLK_P_164") (pintype "passive"))
      (node (ref "rxPI1") (pin "164") (pinfunction "HDMI1_CLK_P_164") (pintype "passive"))
    )
    (net (code "211") (name "Net-(rPI1B-HDMI1_HOTPLUG)") (class "Default")
      (node (ref "J2") (pin "44") (pinfunction "44_44") (pintype "passive"))
      (node (ref "J5") (pin "43") (pinfunction "43_43") (pintype "passive"))
      (node (ref "rPI1") (pin "143") (pinfunction "HDMI1_HOTPLUG_143") (pintype "passive"))
      (node (ref "rxPI1") (pin "143") (pinfunction "HDMI1_HOTPLUG_143") (pintype "passive"))
    )
    (net (code "212") (name "Net-(rPI1B-HDMI1_SCL)") (class "Default")
      (node (ref "J2") (pin "48") (pinfunction "48_48") (pintype "passive"))
      (node (ref "J5") (pin "47") (pinfunction "47_47") (pintype "passive"))
      (node (ref "rPI1") (pin "147") (pinfunction "HDMI1_SCL_147") (pintype "passive"))
      (node (ref "rxPI1") (pin "147") (pinfunction "HDMI1_SCL_147") (pintype "passive"))
    )
    (net (code "213") (name "Net-(rPI1B-HDMI1_SDA)") (class "Default")
      (node (ref "J2") (pin "46") (pinfunction "46_46") (pintype "passive"))
      (node (ref "J5") (pin "45") (pinfunction "45_45") (pintype "passive"))
      (node (ref "rPI1") (pin "145") (pinfunction "HDMI1_SDA_145") (pintype "passive"))
      (node (ref "rxPI1") (pin "145") (pinfunction "HDMI1_SDA_145") (pintype "passive"))
    )
    (net (code "214") (name "Net-(rPI1B-HDMI1_TX0_N)") (class "Default")
      (node (ref "J2") (pin "59") (pinfunction "59_59") (pintype "passive"))
      (node (ref "J5") (pin "60") (pinfunction "60_60") (pintype "passive"))
      (node (ref "rPI1") (pin "160") (pinfunction "HDMI1_TX0_N_160") (pintype "passive"))
      (node (ref "rxPI1") (pin "160") (pinfunction "HDMI1_TX0_N_160") (pintype "passive"))
    )
    (net (code "215") (name "Net-(rPI1B-HDMI1_TX0_P)") (class "Default")
      (node (ref "J2") (pin "57") (pinfunction "57_57") (pintype "passive"))
      (node (ref "J5") (pin "58") (pinfunction "58_58") (pintype "passive"))
      (node (ref "rPI1") (pin "158") (pinfunction "HDMI1_TX0_P_158") (pintype "passive"))
      (node (ref "rxPI1") (pin "158") (pinfunction "HDMI1_TX0_P_158") (pintype "passive"))
    )
    (net (code "216") (name "Net-(rPI1B-HDMI1_TX1_N)") (class "Default")
      (node (ref "J2") (pin "53") (pinfunction "53_53") (pintype "passive"))
      (node (ref "J5") (pin "54") (pinfunction "54_54") (pintype "passive"))
      (node (ref "rPI1") (pin "154") (pinfunction "HDMI1_TX1_N_154") (pintype "passive"))
      (node (ref "rxPI1") (pin "154") (pinfunction "HDMI1_TX1_N_154") (pintype "passive"))
    )
    (net (code "217") (name "Net-(rPI1B-HDMI1_TX1_P)") (class "Default")
      (node (ref "J2") (pin "51") (pinfunction "51_51") (pintype "passive"))
      (node (ref "J5") (pin "52") (pinfunction "52_52") (pintype "passive"))
      (node (ref "rPI1") (pin "152") (pinfunction "HDMI1_TX1_P_152") (pintype "passive"))
      (node (ref "rxPI1") (pin "152") (pinfunction "HDMI1_TX1_P_152") (pintype "passive"))
    )
    (net (code "218") (name "Net-(rPI1B-HDMI1_TX2_N)") (class "Default")
      (node (ref "J2") (pin "47") (pinfunction "47_47") (pintype "passive"))
      (node (ref "J5") (pin "48") (pinfunction "48_48") (pintype "passive"))
      (node (ref "rPI1") (pin "148") (pinfunction "HDMI1_TX2_N_148") (pintype "passive"))
      (node (ref "rxPI1") (pin "148") (pinfunction "HDMI1_TX2_N_148") (pintype "passive"))
    )
    (net (code "219") (name "Net-(rPI1B-HDMI1_TX2_P)") (class "Default")
      (node (ref "J2") (pin "45") (pinfunction "45_45") (pintype "passive"))
      (node (ref "J5") (pin "46") (pinfunction "46_46") (pintype "passive"))
      (node (ref "rPI1") (pin "146") (pinfunction "HDMI1_TX2_P_146") (pintype "passive"))
      (node (ref "rxPI1") (pin "146") (pinfunction "HDMI1_TX2_P_146") (pintype "passive"))
    )
    (net (code "220") (name "Net-(rPI1B-MIPI0_C_N)") (class "Default")
      (node (ref "J2") (pin "28") (pinfunction "28_28") (pintype "passive"))
      (node (ref "J5") (pin "27") (pinfunction "27_27") (pintype "passive"))
      (node (ref "rPI1") (pin "127") (pinfunction "MIPI0_C_N_127") (pintype "passive"))
      (node (ref "rxPI1") (pin "127") (pinfunction "MIPI0_C_N_127") (pintype "passive"))
    )
    (net (code "221") (name "Net-(rPI1B-MIPI0_C_P)") (class "Default")
      (node (ref "J2") (pin "30") (pinfunction "30_30") (pintype "passive"))
      (node (ref "J5") (pin "29") (pinfunction "29_29") (pintype "passive"))
      (node (ref "rPI1") (pin "129") (pinfunction "MIPI0_C_P_129") (pintype "passive"))
      (node (ref "rxPI1") (pin "129") (pinfunction "MIPI0_C_P_129") (pintype "passive"))
    )
    (net (code "222") (name "Net-(rPI1B-MIPI0_D0_N)") (class "Default")
      (node (ref "J2") (pin "16") (pinfunction "16_16") (pintype "passive"))
      (node (ref "J5") (pin "15") (pinfunction "15_15") (pintype "passive"))
      (node (ref "rPI1") (pin "115") (pinfunction "MIPI0_D0_N_115") (pintype "passive"))
      (node (ref "rxPI1") (pin "115") (pinfunction "MIPI0_D0_N_115") (pintype "passive"))
    )
    (net (code "223") (name "Net-(rPI1B-MIPI0_D0_P)") (class "Default")
      (node (ref "J2") (pin "18") (pinfunction "18_18") (pintype "passive"))
      (node (ref "J5") (pin "17") (pinfunction "17_17") (pintype "passive"))
      (node (ref "rPI1") (pin "117") (pinfunction "MIPI0_D0_P_117") (pintype "passive"))
      (node (ref "rxPI1") (pin "117") (pinfunction "MIPI0_D0_P_117") (pintype "passive"))
    )
    (net (code "224") (name "Net-(rPI1B-MIPI0_D1_N)") (class "Default")
      (node (ref "J2") (pin "22") (pinfunction "22_22") (pintype "passive"))
      (node (ref "J5") (pin "21") (pinfunction "21_21") (pintype "passive"))
      (node (ref "rPI1") (pin "121") (pinfunction "MIPI0_D1_N_121") (pintype "passive"))
      (node (ref "rxPI1") (pin "121") (pinfunction "MIPI0_D1_N_121") (pintype "passive"))
    )
    (net (code "225") (name "Net-(rPI1B-MIPI0_D1_P)") (class "Default")
      (node (ref "J2") (pin "24") (pinfunction "24_24") (pintype "passive"))
      (node (ref "J5") (pin "23") (pinfunction "23_23") (pintype "passive"))
      (node (ref "rPI1") (pin "123") (pinfunction "MIPI0_D1_P_123") (pintype "passive"))
      (node (ref "rxPI1") (pin "123") (pinfunction "MIPI0_D1_P_123") (pintype "passive"))
    )
    (net (code "226") (name "Net-(rPI1B-MIPI0_D2_N)") (class "Default")
      (node (ref "J2") (pin "34") (pinfunction "34_34") (pintype "passive"))
      (node (ref "J5") (pin "33") (pinfunction "33_33") (pintype "passive"))
      (node (ref "rPI1") (pin "133") (pinfunction "MIPI0_D2_N_133") (pintype "passive"))
      (node (ref "rxPI1") (pin "133") (pinfunction "MIPI0_D2_N_133") (pintype "passive"))
    )
    (net (code "227") (name "Net-(rPI1B-MIPI0_D2_P)") (class "Default")
      (node (ref "J2") (pin "36") (pinfunction "36_36") (pintype "passive"))
      (node (ref "J5") (pin "35") (pinfunction "35_35") (pintype "passive"))
      (node (ref "rPI1") (pin "135") (pinfunction "MIPI0_D2_P_135") (pintype "passive"))
      (node (ref "rxPI1") (pin "135") (pinfunction "MIPI0_D2_P_135") (pintype "passive"))
    )
    (net (code "228") (name "Net-(rPI1B-MIPI0_D3_N)") (class "Default")
      (node (ref "J2") (pin "40") (pinfunction "40_40") (pintype "passive"))
      (node (ref "J5") (pin "39") (pinfunction "39_39") (pintype "passive"))
      (node (ref "rPI1") (pin "139") (pinfunction "MIPI0_D3_N_139") (pintype "passive"))
      (node (ref "rxPI1") (pin "139") (pinfunction "MIPI0_D3_N_139") (pintype "passive"))
    )
    (net (code "229") (name "Net-(rPI1B-MIPI0_D3_P)") (class "Default")
      (node (ref "J2") (pin "42") (pinfunction "42_42") (pintype "passive"))
      (node (ref "J5") (pin "41") (pinfunction "41_41") (pintype "passive"))
      (node (ref "rPI1") (pin "141") (pinfunction "MIPI0_D3_P_141") (pintype "passive"))
      (node (ref "rxPI1") (pin "141") (pinfunction "MIPI0_D3_P_141") (pintype "passive"))
    )
    (net (code "230") (name "Net-(rPI1B-MIPI1_C_N)") (class "Default")
      (node (ref "J2") (pin "88") (pinfunction "88_88") (pintype "passive"))
      (node (ref "J5") (pin "87") (pinfunction "87_87") (pintype "passive"))
      (node (ref "rPI1") (pin "187") (pinfunction "MIPI1_C_N_187") (pintype "passive"))
      (node (ref "rxPI1") (pin "187") (pinfunction "MIPI1_C_N_187") (pintype "passive"))
    )
    (net (code "231") (name "Net-(rPI1B-MIPI1_C_P)") (class "Default")
      (node (ref "J2") (pin "90") (pinfunction "90_90") (pintype "passive"))
      (node (ref "J5") (pin "89") (pinfunction "89_89") (pintype "passive"))
      (node (ref "rPI1") (pin "189") (pinfunction "MIPI1_C_P_189") (pintype "passive"))
      (node (ref "rxPI1") (pin "189") (pinfunction "MIPI1_C_P_189") (pintype "passive"))
    )
    (net (code "232") (name "Net-(rPI1B-MIPI1_D0_N)") (class "Default")
      (node (ref "J2") (pin "76") (pinfunction "76_76") (pintype "passive"))
      (node (ref "J5") (pin "75") (pinfunction "75_75") (pintype "passive"))
      (node (ref "rPI1") (pin "175") (pinfunction "MIPI1_D0_N_175") (pintype "passive"))
      (node (ref "rxPI1") (pin "175") (pinfunction "MIPI1_D0_N_175") (pintype "passive"))
    )
    (net (code "233") (name "Net-(rPI1B-MIPI1_D0_P)") (class "Default")
      (node (ref "J2") (pin "78") (pinfunction "78_78") (pintype "passive"))
      (node (ref "J5") (pin "77") (pinfunction "77_77") (pintype "passive"))
      (node (ref "rPI1") (pin "177") (pinfunction "MIPI1_D0_P_177") (pintype "passive"))
      (node (ref "rxPI1") (pin "177") (pinfunction "MIPI1_D0_P_177") (pintype "passive"))
    )
    (net (code "234") (name "Net-(rPI1B-MIPI1_D1_N)") (class "Default")
      (node (ref "J2") (pin "82") (pinfunction "82_82") (pintype "passive"))
      (node (ref "J5") (pin "81") (pinfunction "81_81") (pintype "passive"))
      (node (ref "rPI1") (pin "181") (pinfunction "MIPI1_D1_N_181") (pintype "passive"))
      (node (ref "rxPI1") (pin "181") (pinfunction "MIPI1_D1_N_181") (pintype "passive"))
    )
    (net (code "235") (name "Net-(rPI1B-MIPI1_D1_P)") (class "Default")
      (node (ref "J2") (pin "84") (pinfunction "84_84") (pintype "passive"))
      (node (ref "J5") (pin "83") (pinfunction "83_83") (pintype "passive"))
      (node (ref "rPI1") (pin "183") (pinfunction "MIPI1_D1_P_183") (pintype "passive"))
      (node (ref "rxPI1") (pin "183") (pinfunction "MIPI1_D1_P_183") (pintype "passive"))
    )
    (net (code "236") (name "Net-(rPI1B-MIPI1_D2_N)") (class "Default")
      (node (ref "J2") (pin "94") (pinfunction "94_94") (pintype "passive"))
      (node (ref "J5") (pin "93") (pinfunction "93_93") (pintype "passive"))
      (node (ref "rPI1") (pin "193") (pinfunction "MIPI1_D2_N_193") (pintype "passive"))
      (node (ref "rxPI1") (pin "193") (pinfunction "MIPI1_D2_N_193") (pintype "passive"))
    )
    (net (code "237") (name "Net-(rPI1B-MIPI1_D2_P)") (class "Default")
      (node (ref "J2") (pin "96") (pinfunction "96_96") (pintype "passive"))
      (node (ref "J5") (pin "95") (pinfunction "95_95") (pintype "passive"))
      (node (ref "rPI1") (pin "195") (pinfunction "MIPI1_D2_P_195") (pintype "passive"))
      (node (ref "rxPI1") (pin "195") (pinfunction "MIPI1_D2_P_195") (pintype "passive"))
    )
    (net (code "238") (name "Net-(rPI1B-MIPI1_D3_N)") (class "Default")
      (node (ref "J2") (pin "93") (pinfunction "93_93") (pintype "passive"))
      (node (ref "J5") (pin "94") (pinfunction "94_94") (pintype "passive"))
      (node (ref "rPI1") (pin "194") (pinfunction "MIPI1_D3_N_194") (pintype "passive"))
      (node (ref "rxPI1") (pin "194") (pinfunction "MIPI1_D3_N_194") (pintype "passive"))
    )
    (net (code "239") (name "Net-(rPI1B-MIPI1_D3_P)") (class "Default")
      (node (ref "J2") (pin "95") (pinfunction "95_95") (pintype "passive"))
      (node (ref "J5") (pin "96") (pinfunction "96_96") (pintype "passive"))
      (node (ref "rPI1") (pin "196") (pinfunction "MIPI1_D3_P_196") (pintype "passive"))
      (node (ref "rxPI1") (pin "196") (pinfunction "MIPI1_D3_P_196") (pintype "passive"))
    )
    (net (code "240") (name "Net-(rPI1B-PCIE_PWR_EN)") (class "Default")
      (node (ref "J2") (pin "5") (pinfunction "5_5") (pintype "passive"))
      (node (ref "J5") (pin "6") (pinfunction "6_6") (pintype "passive"))
      (node (ref "rPI1") (pin "106") (pinfunction "PCIE_PWR_EN_106") (pintype "passive"))
      (node (ref "rxPI1") (pin "106") (pinfunction "PCIE_PWR_EN_106") (pintype "passive"))
    )
    (net (code "241") (name "Net-(rPI1B-PCIE_nWAKE)") (class "Default")
      (node (ref "J2") (pin "3") (pinfunction "3_3") (pintype "passive"))
      (node (ref "J5") (pin "4") (pinfunction "4_4") (pintype "passive"))
      (node (ref "rPI1") (pin "104") (pinfunction "PCIE_nWAKE_104") (pintype "passive"))
      (node (ref "rxPI1") (pin "104") (pinfunction "PCIE_nWAKE_104") (pintype "passive"))
    )
    (net (code "242") (name "Net-(rPI1B-PCIe_CLK_N)") (class "Default")
      (node (ref "J2") (pin "11") (pinfunction "11_11") (pintype "passive"))
      (node (ref "J5") (pin "12") (pinfunction "12_12") (pintype "passive"))
      (node (ref "rPI1") (pin "112") (pinfunction "PCIe_CLK_N_112") (pintype "passive"))
      (node (ref "rxPI1") (pin "112") (pinfunction "PCIe_CLK_N_112") (pintype "passive"))
    )
    (net (code "243") (name "Net-(rPI1B-PCIe_CLK_P)") (class "Default")
      (node (ref "J2") (pin "9") (pinfunction "9_9") (pintype "passive"))
      (node (ref "J5") (pin "10") (pinfunction "10_10") (pintype "passive"))
      (node (ref "rPI1") (pin "110") (pinfunction "PCIe_CLK_P_110") (pintype "passive"))
      (node (ref "rxPI1") (pin "110") (pinfunction "PCIe_CLK_P_110") (pintype "passive"))
    )
    (net (code "244") (name "Net-(rPI1B-PCIe_CLK_nREQ)") (class "Default")
      (node (ref "J2") (pin "1") (pinfunction "1_1") (pintype "passive"))
      (node (ref "J5") (pin "2") (pinfunction "2_2") (pintype "passive"))
      (node (ref "rPI1") (pin "102") (pinfunction "PCIe_CLK_nREQ_102") (pintype "passive"))
      (node (ref "rxPI1") (pin "102") (pinfunction "PCIe_CLK_nREQ_102") (pintype "passive"))
    )
    (net (code "245") (name "Net-(rPI1B-PCIe_RX_N)") (class "Default")
      (node (ref "J2") (pin "17") (pinfunction "17_17") (pintype "passive"))
      (node (ref "J5") (pin "18") (pinfunction "18_18") (pintype "passive"))
      (node (ref "rPI1") (pin "118") (pinfunction "PCIe_RX_N_118") (pintype "passive"))
      (node (ref "rxPI1") (pin "118") (pinfunction "PCIe_RX_N_118") (pintype "passive"))
    )
    (net (code "246") (name "Net-(rPI1B-PCIe_RX_P)") (class "Default")
      (node (ref "J2") (pin "15") (pinfunction "15_15") (pintype "passive"))
      (node (ref "J5") (pin "16") (pinfunction "16_16") (pintype "passive"))
      (node (ref "rPI1") (pin "116") (pinfunction "PCIe_RX_P_116") (pintype "passive"))
      (node (ref "rxPI1") (pin "116") (pinfunction "PCIe_RX_P_116") (pintype "passive"))
    )
    (net (code "247") (name "Net-(rPI1B-PCIe_TX_N)") (class "Default")
      (node (ref "J2") (pin "23") (pinfunction "23_23") (pintype "passive"))
      (node (ref "J5") (pin "24") (pinfunction "24_24") (pintype "passive"))
      (node (ref "rPI1") (pin "124") (pinfunction "PCIe_TX_N_124") (pintype "passive"))
      (node (ref "rxPI1") (pin "124") (pinfunction "PCIe_TX_N_124") (pintype "passive"))
    )
    (net (code "248") (name "Net-(rPI1B-PCIe_TX_P)") (class "Default")
      (node (ref "J2") (pin "21") (pinfunction "21_21") (pintype "passive"))
      (node (ref "J5") (pin "22") (pinfunction "22_22") (pintype "passive"))
      (node (ref "rPI1") (pin "122") (pinfunction "PCIe_TX_P_122") (pintype "passive"))
      (node (ref "rxPI1") (pin "122") (pinfunction "PCIe_TX_P_122") (pintype "passive"))
    )
    (net (code "249") (name "Net-(rPI1B-PCIe_nRST)") (class "Default")
      (node (ref "J2") (pin "10") (pinfunction "10_10") (pintype "passive"))
      (node (ref "J5") (pin "9") (pinfunction "9_9") (pintype "passive"))
      (node (ref "rPI1") (pin "109") (pinfunction "PCIe_nRST_109") (pintype "passive"))
      (node (ref "rxPI1") (pin "109") (pinfunction "PCIe_nRST_109") (pintype "passive"))
    )
    (net (code "250") (name "Net-(rPI1B-USB2_N)") (class "Default")
      (node (ref "J2") (pin "4") (pinfunction "4_4") (pintype "passive"))
      (node (ref "J5") (pin "3") (pinfunction "3_3") (pintype "passive"))
      (node (ref "rPI1") (pin "103") (pinfunction "USB2_N_103") (pintype "passive"))
      (node (ref "rxPI1") (pin "103") (pinfunction "USB2_N_103") (pintype "passive"))
    )
    (net (code "251") (name "Net-(rPI1B-USB2_P)") (class "Default")
      (node (ref "J2") (pin "6") (pinfunction "6_6") (pintype "passive"))
      (node (ref "J5") (pin "5") (pinfunction "5_5") (pintype "passive"))
      (node (ref "rPI1") (pin "105") (pinfunction "USB2_P_105") (pintype "passive"))
      (node (ref "rxPI1") (pin "105") (pinfunction "USB2_P_105") (pintype "passive"))
    )
    (net (code "252") (name "Net-(rPI1B-USB3-0-D_N)") (class "Default")
      (node (ref "J2") (pin "35") (pinfunction "35_35") (pintype "passive"))
      (node (ref "J5") (pin "36") (pinfunction "36_36") (pintype "passive"))
      (node (ref "rPI1") (pin "136") (pinfunction "USB3-0-D_N_136") (pintype "passive"))
      (node (ref "rxPI1") (pin "136") (pinfunction "USB3-0-D_N_136") (pintype "passive"))
    )
    (net (code "253") (name "Net-(rPI1B-USB3-0-D_P)") (class "Default")
      (node (ref "J2") (pin "33") (pinfunction "33_33") (pintype "passive"))
      (node (ref "J5") (pin "34") (pinfunction "34_34") (pintype "passive"))
      (node (ref "rPI1") (pin "134") (pinfunction "USB3-0-D_P_134") (pintype "passive"))
      (node (ref "rxPI1") (pin "134") (pinfunction "USB3-0-D_P_134") (pintype "passive"))
    )
    (net (code "254") (name "Net-(rPI1B-USB3-0-RX_N)") (class "Default")
      (node (ref "J2") (pin "27") (pinfunction "27_27") (pintype "passive"))
      (node (ref "J5") (pin "28") (pinfunction "28_28") (pintype "passive"))
      (node (ref "rPI1") (pin "128") (pinfunction "USB3-0-RX_N_128") (pintype "passive"))
      (node (ref "rxPI1") (pin "128") (pinfunction "USB3-0-RX_N_128") (pintype "passive"))
    )
    (net (code "255") (name "Net-(rPI1B-USB3-0-RX_P)") (class "Default")
      (node (ref "J2") (pin "29") (pinfunction "29_29") (pintype "passive"))
      (node (ref "J5") (pin "30") (pinfunction "30_30") (pintype "passive"))
      (node (ref "rPI1") (pin "130") (pinfunction "USB3-0-RX_P_130") (pintype "passive"))
      (node (ref "rxPI1") (pin "130") (pinfunction "USB3-0-RX_P_130") (pintype "passive"))
    )
    (net (code "256") (name "Net-(rPI1B-USB3-0-TX_N)") (class "Default")
      (node (ref "J2") (pin "39") (pinfunction "39_39") (pintype "passive"))
      (node (ref "J5") (pin "40") (pinfunction "40_40") (pintype "passive"))
      (node (ref "rPI1") (pin "140") (pinfunction "USB3-0-TX_N_140") (pintype "passive"))
      (node (ref "rxPI1") (pin "140") (pinfunction "USB3-0-TX_N_140") (pintype "passive"))
    )
    (net (code "257") (name "Net-(rPI1B-USB3-0-TX_P)") (class "Default")
      (node (ref "J2") (pin "41") (pinfunction "41_41") (pintype "passive"))
      (node (ref "J5") (pin "42") (pinfunction "42_42") (pintype "passive"))
      (node (ref "rPI1") (pin "142") (pinfunction "USB3-0-TX_P_142") (pintype "passive"))
      (node (ref "rxPI1") (pin "142") (pinfunction "USB3-0-TX_P_142") (pintype "passive"))
    )
    (net (code "258") (name "Net-(rPI1B-USB3-1-D_N)") (class "Default")
      (node (ref "J2") (pin "66") (pinfunction "66_66") (pintype "passive"))
      (node (ref "J5") (pin "65") (pinfunction "65_65") (pintype "passive"))
      (node (ref "rPI1") (pin "165") (pinfunction "USB3-1-D_N_165") (pintype "passive"))
      (node (ref "rxPI1") (pin "165") (pinfunction "USB3-1-D_N_165") (pintype "passive"))
    )
    (net (code "259") (name "Net-(rPI1B-USB3-1-D_P)") (class "Default")
      (node (ref "J2") (pin "64") (pinfunction "64_64") (pintype "passive"))
      (node (ref "J5") (pin "63") (pinfunction "63_63") (pintype "passive"))
      (node (ref "rPI1") (pin "163") (pinfunction "USB3-1-D_P_163") (pintype "passive"))
      (node (ref "rxPI1") (pin "163") (pinfunction "USB3-1-D_P_163") (pintype "passive"))
    )
    (net (code "260") (name "Net-(rPI1B-USB3-1-RX_N)") (class "Default")
      (node (ref "J2") (pin "58") (pinfunction "58_58") (pintype "passive"))
      (node (ref "J5") (pin "57") (pinfunction "57_57") (pintype "passive"))
      (node (ref "rPI1") (pin "157") (pinfunction "USB3-1-RX_N_157") (pintype "passive"))
      (node (ref "rxPI1") (pin "157") (pinfunction "USB3-1-RX_N_157") (pintype "passive"))
    )
    (net (code "261") (name "Net-(rPI1B-USB3-1-RX_P)") (class "Default")
      (node (ref "J2") (pin "60") (pinfunction "60_60") (pintype "passive"))
      (node (ref "J5") (pin "59") (pinfunction "59_59") (pintype "passive"))
      (node (ref "rPI1") (pin "159") (pinfunction "USB3-1-RX_P_159") (pintype "passive"))
      (node (ref "rxPI1") (pin "159") (pinfunction "USB3-1-RX_P_159") (pintype "passive"))
    )
    (net (code "262") (name "Net-(rPI1B-USB3-1-TX_N)") (class "Default")
      (node (ref "J2") (pin "70") (pinfunction "70_70") (pintype "passive"))
      (node (ref "J5") (pin "69") (pinfunction "69_69") (pintype "passive"))
      (node (ref "rPI1") (pin "169") (pinfunction "USB3-1-TX_N_169") (pintype "passive"))
      (node (ref "rxPI1") (pin "169") (pinfunction "USB3-1-TX_N_169") (pintype "passive"))
    )
    (net (code "263") (name "Net-(rPI1B-USB3-1-TX_P)") (class "Default")
      (node (ref "J2") (pin "72") (pinfunction "72_72") (pintype "passive"))
      (node (ref "J5") (pin "71") (pinfunction "71_71") (pintype "passive"))
      (node (ref "rPI1") (pin "171") (pinfunction "USB3-1-TX_P_171") (pintype "passive"))
      (node (ref "rxPI1") (pin "171") (pinfunction "USB3-1-TX_P_171") (pintype "passive"))
    )
    (net (code "264") (name "Net-(rPI1B-USB_OTG_ID)") (class "Default")
      (node (ref "J2") (pin "2") (pinfunction "2_2") (pintype "passive"))
      (node (ref "J5") (pin "1") (pinfunction "1_1") (pintype "passive"))
      (node (ref "rPI1") (pin "101") (pinfunction "USB_OTG_ID_101") (pintype "passive"))
      (node (ref "rxPI1") (pin "101") (pinfunction "USB_OTG_ID_101") (pintype "passive"))
    )
    (net (code "265") (name "Net-(rPI1B-VBUS_EN)") (class "Default")
      (node (ref "J2") (pin "12") (pinfunction "12_12") (pintype "passive"))
      (node (ref "J5") (pin "11") (pinfunction "11_11") (pintype "passive"))
      (node (ref "rPI1") (pin "111") (pinfunction "VBUS_EN_111") (pintype "passive"))
      (node (ref "rxPI1") (pin "111") (pinfunction "VBUS_EN_111") (pintype "passive"))
    )
    (net (code "266") (name "Net-(rxPI1C-BT_HOST_WAKE)") (class "Default")
      (node (ref "J3") (pin "86") (pinfunction "86_86") (pintype "passive"))
      (node (ref "rxPI1") (pin "285") (pinfunction "BT_HOST_WAKE_285") (pintype "passive"))
    )
    (net (code "267") (name "Net-(rxPI1C-BT_REG_ON_H)") (class "Default")
      (node (ref "J3") (pin "97") (pinfunction "97_97") (pintype "passive"))
      (node (ref "rxPI1") (pin "298") (pinfunction "BT_REG_ON_H_298") (pintype "passive"))
    )
    (net (code "268") (name "Net-(rxPI1C-CC_INT0_L)") (class "Default")
      (node (ref "J3") (pin "95") (pinfunction "95_95") (pintype "passive"))
      (node (ref "rxPI1") (pin "296") (pinfunction "CC_INT0_L_296") (pintype "passive"))
    )
    (net (code "269") (name "Net-(rxPI1C-GPIO0_C2)") (class "Default")
      (node (ref "J3") (pin "94") (pinfunction "94_94") (pintype "passive"))
      (node (ref "rxPI1") (pin "293") (pinfunction "GPIO0_C2_293") (pintype "passive"))
    )
    (net (code "270") (name "Net-(rxPI1C-GPIO0_D3)") (class "Default")
      (node (ref "J3") (pin "93") (pinfunction "93_93") (pintype "passive"))
      (node (ref "rxPI1") (pin "294") (pinfunction "GPIO0_D3_294") (pintype "passive"))
    )
    (net (code "271") (name "Net-(rxPI1C-GPIO1_B6_CAM2_CLK)") (class "Default")
      (node (ref "J3") (pin "9") (pinfunction "9_9") (pintype "passive"))
      (node (ref "rxPI1") (pin "210") (pinfunction "GPIO1_B6_CAM2_CLK_210") (pintype "passive"))
    )
    (net (code "272") (name "Net-(rxPI1C-GPIO1_B7)") (class "Default")
      (node (ref "J3") (pin "11") (pinfunction "11_11") (pintype "passive"))
      (node (ref "rxPI1") (pin "212") (pinfunction "GPIO1_B7_212") (pintype "passive"))
    )
    (net (code "273") (name "Net-(rxPI1C-GPIO1_C1)") (class "Default")
      (node (ref "J3") (pin "19") (pinfunction "19_19") (pintype "passive"))
      (node (ref "rxPI1") (pin "220") (pinfunction "GPIO1_C1_220") (pintype "passive"))
    )
    (net (code "274") (name "Net-(rxPI1C-GPIO1_C4_S)") (class "Default")
      (node (ref "J3") (pin "80") (pinfunction "80_80") (pintype "passive"))
      (node (ref "rxPI1") (pin "279") (pinfunction "GPIO1_C4_S_279") (pintype "passive"))
    )
    (net (code "275") (name "Net-(rxPI1C-GPIO1_C6_S)") (class "Default")
      (node (ref "J3") (pin "76") (pinfunction "76_76") (pintype "passive"))
      (node (ref "rxPI1") (pin "275") (pinfunction "GPIO1_C6_S_275") (pintype "passive"))
    )
    (net (code "276") (name "Net-(rxPI1C-GPIO1_D0)") (class "Default")
      (node (ref "J3") (pin "43") (pinfunction "43_43") (pintype "passive"))
      (node (ref "rxPI1") (pin "244") (pinfunction "GPIO1_D0_244") (pintype "passive"))
    )
    (net (code "277") (name "Net-(rxPI1C-GPIO1_D1)") (class "Default")
      (node (ref "J3") (pin "45") (pinfunction "45_45") (pintype "passive"))
      (node (ref "rxPI1") (pin "246") (pinfunction "GPIO1_D1_246") (pintype "passive"))
    )
    (net (code "278") (name "Net-(rxPI1C-GPIO1_D2)") (class "Default")
      (node (ref "J3") (pin "84") (pinfunction "84_84") (pintype "passive"))
      (node (ref "rxPI1") (pin "283") (pinfunction "GPIO1_D2_283") (pintype "passive"))
    )
    (net (code "279") (name "Net-(rxPI1C-GPIO1_D5_S)") (class "Default")
      (node (ref "J3") (pin "78") (pinfunction "78_78") (pintype "passive"))
      (node (ref "rxPI1") (pin "277") (pinfunction "GPIO1_D5_S_277") (pintype "passive"))
    )
    (net (code "280") (name "Net-(rxPI1C-GPIO3_B7)") (class "Default")
      (node (ref "J3") (pin "5") (pinfunction "5_5") (pintype "passive"))
      (node (ref "rxPI1") (pin "206") (pinfunction "GPIO3_B7_206") (pintype "passive"))
    )
    (net (code "281") (name "Net-(rxPI1C-GPIO3_C0)") (class "Default")
      (node (ref "J3") (pin "3") (pinfunction "3_3") (pintype "passive"))
      (node (ref "rxPI1") (pin "204") (pinfunction "GPIO3_C0_204") (pintype "passive"))
    )
    (net (code "282") (name "Net-(rxPI1C-GPIO4_A4)") (class "Default")
      (node (ref "J3") (pin "37") (pinfunction "37_37") (pintype "passive"))
      (node (ref "rxPI1") (pin "238") (pinfunction "GPIO4_A4_238") (pintype "passive"))
    )
    (net (code "283") (name "Net-(rxPI1C-GPIO4_A5)") (class "Default")
      (node (ref "J3") (pin "39") (pinfunction "39_39") (pintype "passive"))
      (node (ref "rxPI1") (pin "240") (pinfunction "GPIO4_A5_240") (pintype "passive"))
    )
    (net (code "284") (name "Net-(rxPI1C-GPIO4_A6)") (class "Default")
      (node (ref "J3") (pin "90") (pinfunction "90_90") (pintype "passive"))
      (node (ref "rxPI1") (pin "289") (pinfunction "GPIO4_A6_289") (pintype "passive"))
    )
    (net (code "285") (name "Net-(rxPI1C-GPIO4_A7)") (class "Default")
      (node (ref "J3") (pin "88") (pinfunction "88_88") (pintype "passive"))
      (node (ref "rxPI1") (pin "287") (pinfunction "GPIO4_A7_287") (pintype "passive"))
    )
    (net (code "286") (name "Net-(rxPI1C-HP_DET_L)") (class "Default")
      (node (ref "J3") (pin "35") (pinfunction "35_35") (pintype "passive"))
      (node (ref "rxPI1") (pin "236") (pinfunction "HP_DET_L_236") (pintype "passive"))
    )
    (net (code "287") (name "Net-(rxPI1C-I2C6_SCL_M3)") (class "Default")
      (node (ref "J3") (pin "72") (pinfunction "72_72") (pintype "passive"))
      (node (ref "rxPI1") (pin "271") (pinfunction "I2C6_SCL_M3_271") (pintype "passive"))
    )
    (net (code "288") (name "Net-(rxPI1C-I2C6_SDA_M3)") (class "Default")
      (node (ref "J3") (pin "70") (pinfunction "70_70") (pintype "passive"))
      (node (ref "rxPI1") (pin "269") (pinfunction "I2C6_SDA_M3_269") (pintype "passive"))
    )
    (net (code "289") (name "Net-(rxPI1C-LCD_PWREN_H)") (class "Default")
      (node (ref "J3") (pin "33") (pinfunction "33_33") (pintype "passive"))
      (node (ref "rxPI1") (pin "234") (pinfunction "LCD_PWREN_H_234") (pintype "passive"))
    )
    (net (code "290") (name "Net-(rxPI1C-PWM11_M3)") (class "Default")
      (node (ref "J3") (pin "17") (pinfunction "17_17") (pintype "passive"))
      (node (ref "rxPI1") (pin "218") (pinfunction "PWM11_M3_218") (pintype "passive"))
    )
    (net (code "291") (name "Net-(rxPI1C-RTC_INT_L)") (class "Default")
      (node (ref "J3") (pin "82") (pinfunction "82_82") (pintype "passive"))
      (node (ref "rxPI1") (pin "281") (pinfunction "RTC_INT_L_281") (pintype "passive"))
    )
    (net (code "292") (name "Net-(rxPI1C-SARADC_VIN0_KEY{slash}RECOVERY)") (class "Default")
      (node (ref "J3") (pin "25") (pinfunction "25_25") (pintype "passive"))
      (node (ref "rxPI1") (pin "226") (pinfunction "SARADC_VIN0_KEY/RECOVERY_226") (pintype "passive"))
    )
    (net (code "293") (name "Net-(rxPI1C-SARADC_VIN1_DC)") (class "Default")
      (node (ref "J3") (pin "27") (pinfunction "27_27") (pintype "passive"))
      (node (ref "rxPI1") (pin "228") (pinfunction "SARADC_VIN1_DC_228") (pintype "passive"))
    )
    (net (code "294") (name "Net-(rxPI1C-SARADC_VIN2_HP_HOOK)") (class "Default")
      (node (ref "J3") (pin "29") (pinfunction "29_29") (pintype "passive"))
      (node (ref "rxPI1") (pin "230") (pinfunction "SARADC_VIN2_HP_HOOK_230") (pintype "passive"))
    )
    (net (code "295") (name "Net-(rxPI1C-SDMMC_DET_L)") (class "Default")
      (node (ref "J3") (pin "73") (pinfunction "73_73") (pintype "passive"))
      (node (ref "rxPI1") (pin "274") (pinfunction "SDMMC_DET_L_274") (pintype "passive"))
    )
    (net (code "296") (name "Net-(rxPI1C-TYPEC0_OTG_VBUSDET)") (class "Default")
      (node (ref "J3") (pin "98") (pinfunction "98_98") (pintype "passive"))
      (node (ref "rxPI1") (pin "297") (pinfunction "TYPEC0_OTG_VBUSDET_297") (pintype "passive"))
    )
    (net (code "297") (name "Net-(rxPI1C-TYPEC0_SBU1)") (class "Default")
      (node (ref "J3") (pin "4") (pinfunction "4_4") (pintype "passive"))
      (node (ref "rxPI1") (pin "203") (pinfunction "TYPEC0_SBU1_203") (pintype "passive"))
    )
    (net (code "298") (name "Net-(rxPI1C-TYPEC0_SBU1_DC)") (class "Default")
      (node (ref "J3") (pin "7") (pinfunction "7_7") (pintype "passive"))
      (node (ref "rxPI1") (pin "208") (pinfunction "TYPEC0_SBU1_DC_208") (pintype "passive"))
    )
    (net (code "299") (name "Net-(rxPI1C-TYPEC0_SBU2)") (class "Default")
      (node (ref "J3") (pin "6") (pinfunction "6_6") (pintype "passive"))
      (node (ref "rxPI1") (pin "205") (pinfunction "TYPEC0_SBU2_205") (pintype "passive"))
    )
    (net (code "300") (name "Net-(rxPI1C-TYPEC0_SBU2_DC)") (class "Default")
      (node (ref "J3") (pin "13") (pinfunction "13_13") (pintype "passive"))
      (node (ref "rxPI1") (pin "214") (pinfunction "TYPEC0_SBU2_DC_214") (pintype "passive"))
    )
    (net (code "301") (name "Net-(rxPI1C-TYPEC0_SSRX1N)") (class "Default")
      (node (ref "J3") (pin "12") (pinfunction "12_12") (pintype "passive"))
      (node (ref "rxPI1") (pin "211") (pinfunction "TYPEC0_SSRX1N_211") (pintype "passive"))
    )
    (net (code "302") (name "Net-(rxPI1C-TYPEC0_SSRX1P)") (class "Default")
      (node (ref "J3") (pin "10") (pinfunction "10_10") (pintype "passive"))
      (node (ref "rxPI1") (pin "209") (pinfunction "TYPEC0_SSRX1P_209") (pintype "passive"))
    )
    (net (code "303") (name "Net-(rxPI1C-TYPEC0_SSRX2N)") (class "Default")
      (node (ref "J3") (pin "24") (pinfunction "24_24") (pintype "passive"))
      (node (ref "rxPI1") (pin "223") (pinfunction "TYPEC0_SSRX2N_223") (pintype "passive"))
    )
    (net (code "304") (name "Net-(rxPI1C-TYPEC0_SSRX2P)") (class "Default")
      (node (ref "J3") (pin "22") (pinfunction "22_22") (pintype "passive"))
      (node (ref "rxPI1") (pin "221") (pinfunction "TYPEC0_SSRX2P_221") (pintype "passive"))
    )
    (net (code "305") (name "Net-(rxPI1C-TYPEC0_SSTX1N)") (class "Default")
      (node (ref "J3") (pin "18") (pinfunction "18_18") (pintype "passive"))
      (node (ref "rxPI1") (pin "217") (pinfunction "TYPEC0_SSTX1N_217") (pintype "passive"))
    )
    (net (code "306") (name "Net-(rxPI1C-TYPEC0_SSTX1P)") (class "Default")
      (node (ref "J3") (pin "16") (pinfunction "16_16") (pintype "passive"))
      (node (ref "rxPI1") (pin "215") (pinfunction "TYPEC0_SSTX1P_215") (pintype "passive"))
    )
    (net (code "307") (name "Net-(rxPI1C-TYPEC0_SSTX2N)") (class "Default")
      (node (ref "J3") (pin "30") (pinfunction "30_30") (pintype "passive"))
      (node (ref "rxPI1") (pin "229") (pinfunction "TYPEC0_SSTX2N_229") (pintype "passive"))
    )
    (net (code "308") (name "Net-(rxPI1C-TYPEC0_SSTX2P)") (class "Default")
      (node (ref "J3") (pin "28") (pinfunction "28_28") (pintype "passive"))
      (node (ref "rxPI1") (pin "227") (pinfunction "TYPEC0_SSTX2P_227") (pintype "passive"))
    )
    (net (code "309") (name "Net-(rxPI1C-TYPEC5V_PWREN_H)") (class "Default")
      (node (ref "J3") (pin "96") (pinfunction "96_96") (pintype "passive"))
      (node (ref "rxPI1") (pin "295") (pinfunction "TYPEC5V_PWREN_H_295") (pintype "passive"))
    )
    (net (code "310") (name "Net-(rxPI1C-USB20_HOST0_DM)") (class "Default")
      (node (ref "J3") (pin "66") (pinfunction "66_66") (pintype "passive"))
      (node (ref "rxPI1") (pin "265") (pinfunction "USB20_HOST0_DM_265") (pintype "passive"))
    )
    (net (code "311") (name "Net-(rxPI1C-USB20_HOST0_DP)") (class "Default")
      (node (ref "J3") (pin "64") (pinfunction "64_64") (pintype "passive"))
      (node (ref "rxPI1") (pin "263") (pinfunction "USB20_HOST0_DP_263") (pintype "passive"))
    )
    (net (code "312") (name "Net-(rxPI1C-USB20_HOST1_DM)") (class "Default")
      (node (ref "J3") (pin "48") (pinfunction "48_48") (pintype "passive"))
      (node (ref "rxPI1") (pin "247") (pinfunction "USB20_HOST1_DM_247") (pintype "passive"))
    )
    (net (code "313") (name "Net-(rxPI1C-USB20_HOST1_DP)") (class "Default")
      (node (ref "J3") (pin "46") (pinfunction "46_46") (pintype "passive"))
      (node (ref "rxPI1") (pin "245") (pinfunction "USB20_HOST1_DP_245") (pintype "passive"))
    )
    (net (code "314") (name "Net-(rxPI1C-VCC_SD_3V3_S3)") (class "Default")
      (node (ref "J3") (pin "91") (pinfunction "91_91") (pintype "passive"))
      (node (ref "rxPI1") (pin "292") (pinfunction "VCC_SD_3V3_S3_292") (pintype "passive"))
    )
    (net (code "315") (name "Net-(rxPI1C-WIFI_PWR_EN)") (class "Default")
      (node (ref "J3") (pin "23") (pinfunction "23_23") (pintype "passive"))
      (node (ref "rxPI1") (pin "224") (pinfunction "WIFI_PWR_EN_224") (pintype "passive"))
    )
    (net (code "316") (name "PCIe_CLK_N") (class "Default")
      (node (ref "J3") (pin "42") (pinfunction "42_42") (pintype "passive"))
      (node (ref "J6") (pin "55") (pinfunction "REFCLKn_55") (pintype "passive"))
      (node (ref "M.1") (pin "55") (pinfunction "REFCLKn_55") (pintype "passive"))
      (node (ref "rxPI1") (pin "241") (pinfunction "PCIE20_2_REFCLKN_241") (pintype "passive"))
    )
    (net (code "317") (name "PCIe_CLK_P") (class "Default")
      (node (ref "J3") (pin "40") (pinfunction "40_40") (pintype "passive"))
      (node (ref "J6") (pin "53") (pinfunction "REFCLKp_53") (pintype "passive"))
      (node (ref "M.1") (pin "53") (pinfunction "REFCLKp_53") (pintype "passive"))
      (node (ref "rxPI1") (pin "239") (pinfunction "PCIE20_2_REFCLKP_239") (pintype "passive"))
    )
    (net (code "318") (name "PCIe_CLK_nREQ_M2") (class "Default")
      (node (ref "J1") (pin "98") (pinfunction "98_98") (pintype "passive"))
      (node (ref "J4") (pin "97") (pinfunction "97_97") (pintype "passive"))
      (node (ref "J6") (pin "52") (pinfunction "CLKREQ_52") (pintype "passive"))
      (node (ref "M.1") (pin "52") (pinfunction "CLKREQ_52") (pintype "passive"))
      (node (ref "rPI1") (pin "97") (pinfunction "Camera_GPIO_97") (pintype "passive"))
      (node (ref "rxPI1") (pin "97") (pinfunction "Camera_GPIO_97") (pintype "passive"))
    )
    (net (code "319") (name "PCIe_RX_N") (class "Default")
      (node (ref "J3") (pin "60") (pinfunction "60_60") (pintype "passive"))
      (node (ref "J6") (pin "47") (pinfunction "PERn0_47") (pintype "passive"))
      (node (ref "M.1") (pin "47") (pinfunction "PERn0_47") (pintype "passive"))
      (node (ref "rxPI1") (pin "259") (pinfunction "C42_-_RXN_259") (pintype "passive"))
    )
    (net (code "320") (name "PCIe_RX_P") (class "Default")
      (node (ref "J3") (pin "58") (pinfunction "58_58") (pintype "passive"))
      (node (ref "J6") (pin "49") (pinfunction "PERp0_49") (pintype "passive"))
      (node (ref "M.1") (pin "49") (pinfunction "PERp0_49") (pintype "passive"))
      (node (ref "rxPI1") (pin "257") (pinfunction "D42_-_RXP_257") (pintype "passive"))
    )
    (net (code "321") (name "PCIe_TX_N") (class "Default")
      (node (ref "J3") (pin "54") (pinfunction "54_54") (pintype "passive"))
      (node (ref "J6") (pin "41") (pinfunction "PETn0_41") (pintype "passive"))
      (node (ref "M.1") (pin "41") (pinfunction "PETn0_41") (pintype "passive"))
      (node (ref "rxPI1") (pin "253") (pinfunction "D41_-_TXN_253") (pintype "passive"))
    )
    (net (code "322") (name "PCIe_TX_P") (class "Default")
      (node (ref "J3") (pin "52") (pinfunction "52_52") (pintype "passive"))
      (node (ref "J6") (pin "43") (pinfunction "PETp0_43") (pintype "passive"))
      (node (ref "M.1") (pin "43") (pinfunction "PETp0_43") (pintype "passive"))
      (node (ref "rxPI1") (pin "251") (pinfunction "E41_-_TXP_251") (pintype "passive"))
    )
    (net (code "323") (name "PCIe_WAKE_M2") (class "Default")
      (node (ref "J1") (pin "28") (pinfunction "28_28") (pintype "passive"))
      (node (ref "J4") (pin "27") (pinfunction "27_27") (pintype "passive"))
      (node (ref "J6") (pin "50") (pinfunction "PEWAKE_50") (pintype "passive"))
      (node (ref "M.1") (pin "50") (pinfunction "PEWAKE_50") (pintype "passive"))
      (node (ref "rPI1") (pin "27") (pinfunction "GPIO20_27") (pintype "passive"))
      (node (ref "rxPI1") (pin "27") (pinfunction "GPIO20_27") (pintype "passive"))
    )
    (net (code "324") (name "PCIe_nRST_M2") (class "Default")
      (node (ref "J1") (pin "48") (pinfunction "48_48") (pintype "passive"))
      (node (ref "J4") (pin "47") (pinfunction "47_47") (pintype "passive"))
      (node (ref "J6") (pin "54") (pinfunction "PERST_54") (pintype "passive"))
      (node (ref "M.1") (pin "54") (pinfunction "PERST_54") (pintype "passive"))
      (node (ref "rPI1") (pin "47") (pinfunction "GPIO23_47") (pintype "passive"))
      (node (ref "rxPI1") (pin "47") (pinfunction "GPIO23_47") (pintype "passive"))
    )
  )
)
